# easy_bee_counter.net
KiCad netlist of a schematic drawn in EAGLE
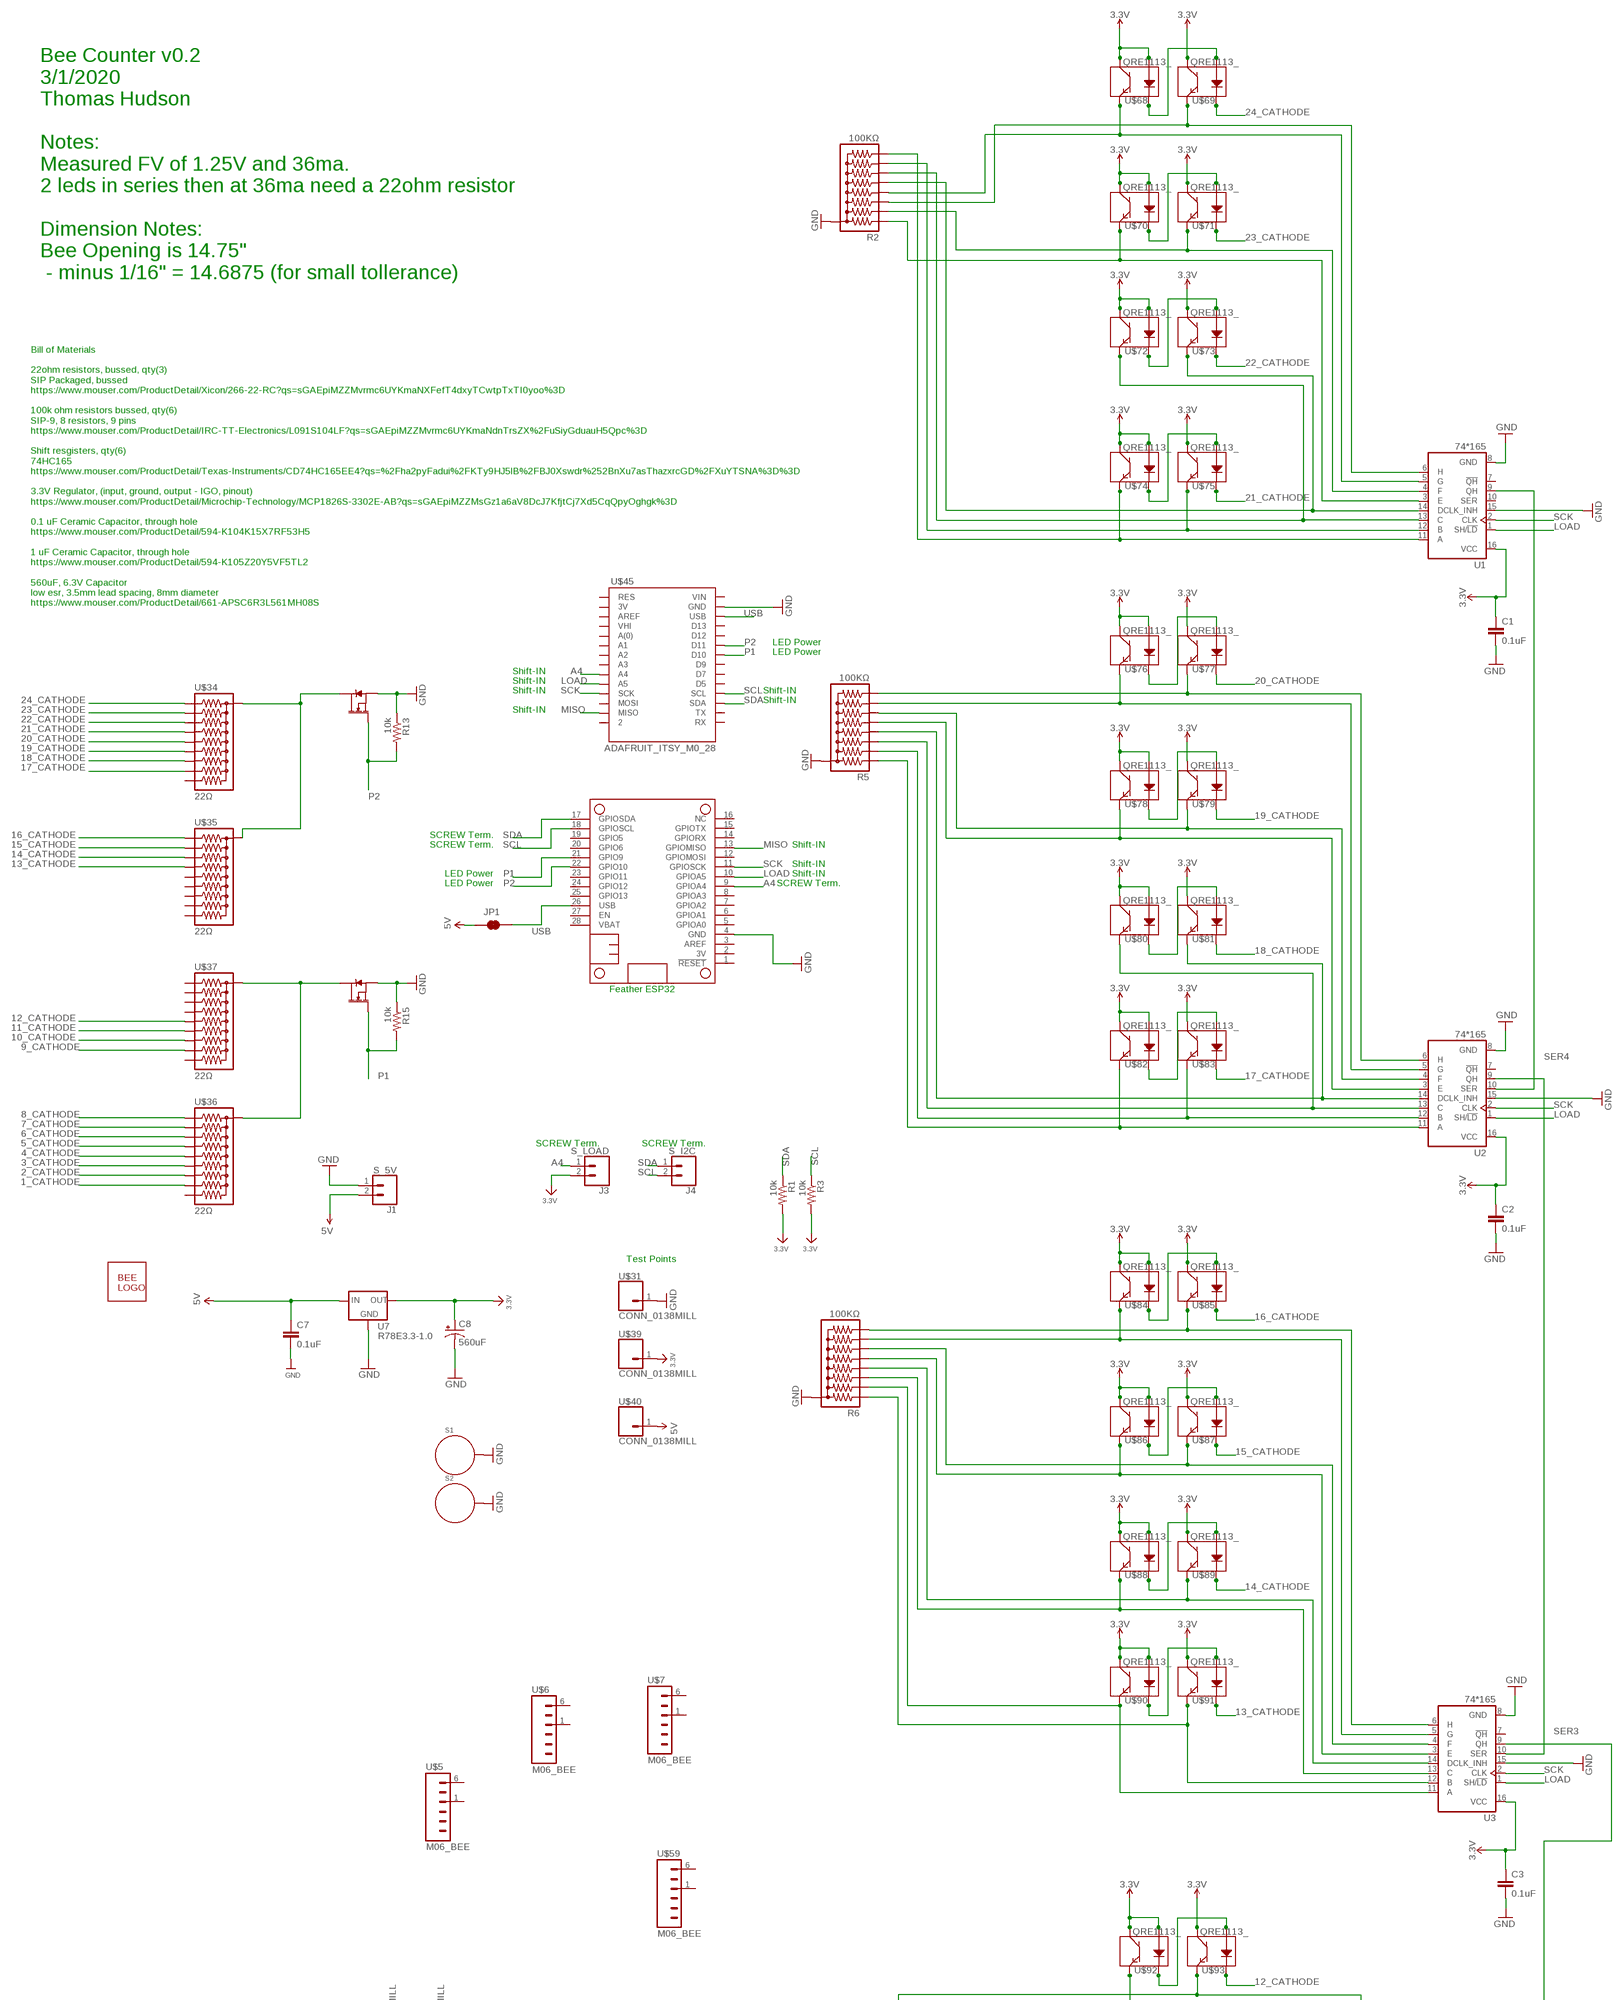
[diagram p0: schematic, sheet 1, part 1 of 2]
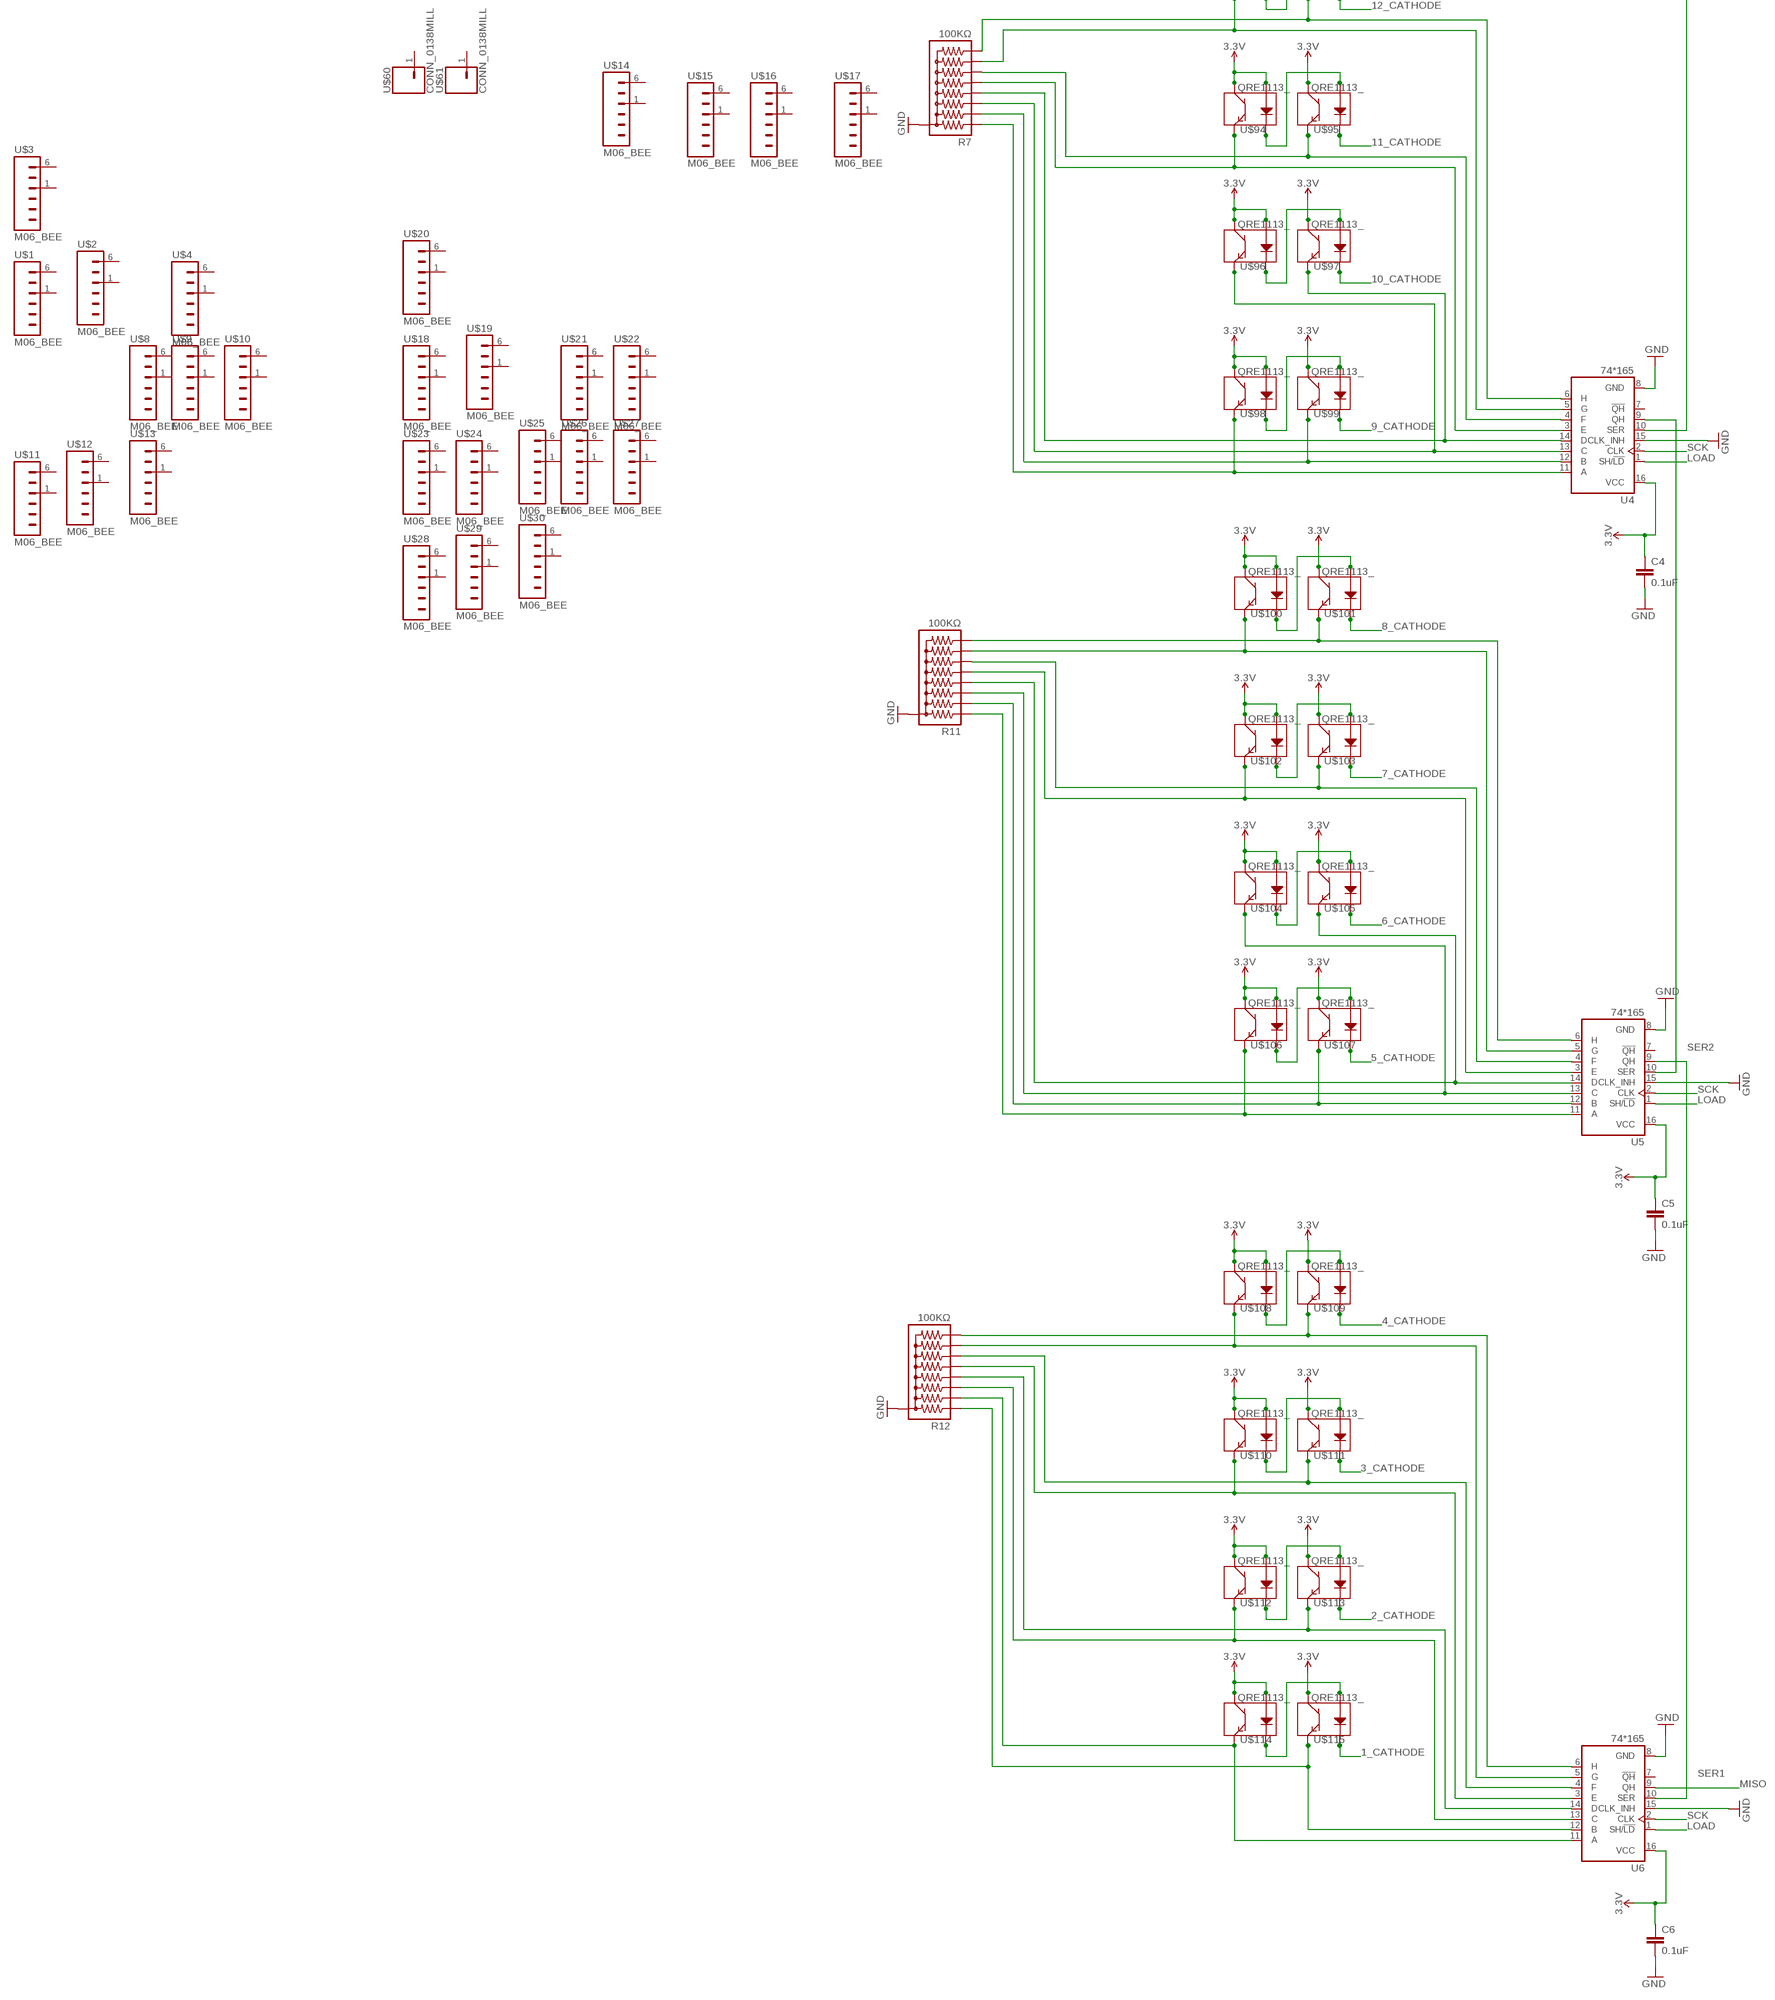
[diagram p1: schematic, sheet 1, part 2 of 2]

(export (version "E")
  (design (tool "Eeschema 10.0.6"))
  (components
    (comp (ref "C1")
      (value "0.1uF")
      (footprint "eagle-import:CAP-PTH-SMALL-KIT")
      (libsource (lib "eagle-import") (part "0.1UF-KIT-EZ-50V-20%"))
    )
    (comp (ref "C2")
      (value "0.1uF")
      (footprint "eagle-import:CAP-PTH-SMALL-KIT")
      (libsource (lib "eagle-import") (part "0.1UF-KIT-EZ-50V-20%"))
    )
    (comp (ref "C3")
      (value "0.1uF")
      (footprint "eagle-import:CAP-PTH-SMALL-KIT")
      (libsource (lib "eagle-import") (part "0.1UF-KIT-EZ-50V-20%"))
    )
    (comp (ref "C4")
      (value "0.1uF")
      (footprint "eagle-import:CAP-PTH-SMALL-KIT")
      (libsource (lib "eagle-import") (part "0.1UF-KIT-EZ-50V-20%"))
    )
    (comp (ref "C5")
      (value "0.1uF")
      (footprint "eagle-import:CAP-PTH-SMALL-KIT")
      (libsource (lib "eagle-import") (part "0.1UF-KIT-EZ-50V-20%"))
    )
    (comp (ref "C6")
      (value "0.1uF")
      (footprint "eagle-import:CAP-PTH-SMALL-KIT")
      (libsource (lib "eagle-import") (part "0.1UF-KIT-EZ-50V-20%"))
    )
    (comp (ref "C7")
      (value "0.1uF")
      (footprint "eagle-import:CAP-PTH-SMALL-KIT")
      (libsource (lib "eagle-import") (part "0.1UF-KIT-EZ-50V-20%"))
    )
    (comp (ref "C8")
      (value "560uF")
      (footprint "eagle-import:E3,5-8")
      (libsource (lib "eagle-import") (part "CPOL-USE3.5-8"))
    )
    (comp (ref "J1")
      (value "S_5V")
      (footprint "eagle-import:SCREWTERMINAL-5MM-2")
      (libsource (lib "eagle-import") (part "CONN_025MM"))
    )
    (comp (ref "J3")
      (value "S_LOAD")
      (footprint "eagle-import:SCREWTERMINAL-5MM-2")
      (libsource (lib "eagle-import") (part "CONN_025MM"))
    )
    (comp (ref "J4")
      (value "S_I2C")
      (footprint "eagle-import:SCREWTERMINAL-5MM-2")
      (libsource (lib "eagle-import") (part "CONN_025MM"))
    )
    (comp (ref "JP1")
      (value "JUMPER-SMT_2_NC_TRACE_SILK")
      (footprint "eagle-import:SMT-JUMPER_2_NC_TRACE_SILK")
      (libsource (lib "eagle-import") (part "JUMPER-SMT_2_NC_TRACE_SILK"))
    )
    (comp (ref "MS2")
      (value "FEATHERWING_NODIM")
      (footprint "eagle-import:FEATHERWING_DIM")
      (libsource (lib "eagle-import") (part "FEATHERWING_NODIM"))
    )
    (comp (ref "Q6")
      (value "60V/32A/35mΩ")
      (footprint "eagle-import:TO220V")
      (libsource (lib "eagle-import") (part "MOSFET-NCH-FQP30N06L"))
    )
    (comp (ref "Q7")
      (value "60V/32A/35mΩ")
      (footprint "eagle-import:TO220V")
      (libsource (lib "eagle-import") (part "MOSFET-NCH-FQP30N06L"))
    )
    (comp (ref "R1")
      (value "10k")
      (footprint "eagle-import:AXIAL-0.3")
      (libsource (lib "eagle-import") (part "RESISTORAXIAL-0.3"))
    )
    (comp (ref "R2")
      (value "100KΩ")
      (footprint "eagle-import:RPACK-SIP-PTH-8")
      (libsource (lib "eagle-import") (part "RPACK-BUSSED-8-SIP-PTH-8"))
    )
    (comp (ref "R3")
      (value "10k")
      (footprint "eagle-import:AXIAL-0.3")
      (libsource (lib "eagle-import") (part "RESISTORAXIAL-0.3"))
    )
    (comp (ref "R5")
      (value "100KΩ")
      (footprint "eagle-import:RPACK-SIP-PTH-8")
      (libsource (lib "eagle-import") (part "RPACK-BUSSED-8-SIP-PTH-8"))
    )
    (comp (ref "R6")
      (value "100KΩ")
      (footprint "eagle-import:RPACK-SIP-PTH-8")
      (libsource (lib "eagle-import") (part "RPACK-BUSSED-8-SIP-PTH-8"))
    )
    (comp (ref "R7")
      (value "100KΩ")
      (footprint "eagle-import:RPACK-SIP-PTH-8")
      (libsource (lib "eagle-import") (part "RPACK-BUSSED-8-SIP-PTH-8"))
    )
    (comp (ref "R11")
      (value "100KΩ")
      (footprint "eagle-import:RPACK-SIP-PTH-8")
      (libsource (lib "eagle-import") (part "RPACK-BUSSED-8-SIP-PTH-8"))
    )
    (comp (ref "R12")
      (value "100KΩ")
      (footprint "eagle-import:RPACK-SIP-PTH-8")
      (libsource (lib "eagle-import") (part "RPACK-BUSSED-8-SIP-PTH-8"))
    )
    (comp (ref "R13")
      (value "10k")
      (footprint "eagle-import:AXIAL-0.3")
      (libsource (lib "eagle-import") (part "RESISTORAXIAL-0.3"))
    )
    (comp (ref "R15")
      (value "10k")
      (footprint "eagle-import:AXIAL-0.3")
      (libsource (lib "eagle-import") (part "RESISTORAXIAL-0.3"))
    )
    (comp (ref "S1")
      (value "STANDOFF_ELECTRICAL5-32")
      (footprint "eagle-import:STANDOFF_ELECTRICAL_5_32")
      (libsource (lib "eagle-import") (part "STANDOFF_ELECTRICAL5-32"))
    )
    (comp (ref "S2")
      (value "STANDOFF_ELECTRICAL5-32")
      (footprint "eagle-import:STANDOFF_ELECTRICAL_5_32")
      (libsource (lib "eagle-import") (part "STANDOFF_ELECTRICAL5-32"))
    )
    (comp (ref "U$1")
      (value "M06_BEE")
      (footprint "eagle-import:1X06_BEE")
      (libsource (lib "eagle-import") (part "M06_BEE"))
    )
    (comp (ref "U$2")
      (value "M06_BEE")
      (footprint "eagle-import:1X06_BEE")
      (libsource (lib "eagle-import") (part "M06_BEE"))
    )
    (comp (ref "U$3")
      (value "M06_BEE")
      (footprint "eagle-import:1X06_BEE")
      (libsource (lib "eagle-import") (part "M06_BEE"))
    )
    (comp (ref "U$4")
      (value "M06_BEE")
      (footprint "eagle-import:1X06_BEE")
      (libsource (lib "eagle-import") (part "M06_BEE"))
    )
    (comp (ref "U$5")
      (value "M06_BEE")
      (footprint "eagle-import:1X06_BEE")
      (libsource (lib "eagle-import") (part "M06_BEE"))
    )
    (comp (ref "U$6")
      (value "M06_BEE")
      (footprint "eagle-import:1X06_BEE")
      (libsource (lib "eagle-import") (part "M06_BEE"))
    )
    (comp (ref "U$7")
      (value "M06_BEE")
      (footprint "eagle-import:1X06_BEE")
      (libsource (lib "eagle-import") (part "M06_BEE"))
    )
    (comp (ref "U$8")
      (value "M06_BEE")
      (footprint "eagle-import:1X06_BEE")
      (libsource (lib "eagle-import") (part "M06_BEE"))
    )
    (comp (ref "U$9")
      (value "M06_BEE")
      (footprint "eagle-import:1X06_BEE")
      (libsource (lib "eagle-import") (part "M06_BEE"))
    )
    (comp (ref "U$10")
      (value "M06_BEE")
      (footprint "eagle-import:1X06_BEE")
      (libsource (lib "eagle-import") (part "M06_BEE"))
    )
    (comp (ref "U$11")
      (value "M06_BEE")
      (footprint "eagle-import:1X06_BEE")
      (libsource (lib "eagle-import") (part "M06_BEE"))
    )
    (comp (ref "U$12")
      (value "M06_BEE")
      (footprint "eagle-import:1X06_BEE")
      (libsource (lib "eagle-import") (part "M06_BEE"))
    )
    (comp (ref "U$13")
      (value "M06_BEE")
      (footprint "eagle-import:1X06_BEE")
      (libsource (lib "eagle-import") (part "M06_BEE"))
    )
    (comp (ref "U$14")
      (value "M06_BEE")
      (footprint "eagle-import:1X06_BEE")
      (libsource (lib "eagle-import") (part "M06_BEE"))
    )
    (comp (ref "U$15")
      (value "M06_BEE")
      (footprint "eagle-import:1X06_BEE")
      (libsource (lib "eagle-import") (part "M06_BEE"))
    )
    (comp (ref "U$16")
      (value "M06_BEE")
      (footprint "eagle-import:1X06_BEE")
      (libsource (lib "eagle-import") (part "M06_BEE"))
    )
    (comp (ref "U$17")
      (value "M06_BEE")
      (footprint "eagle-import:1X06_BEE")
      (libsource (lib "eagle-import") (part "M06_BEE"))
    )
    (comp (ref "U$18")
      (value "M06_BEE")
      (footprint "eagle-import:1X06_BEE")
      (libsource (lib "eagle-import") (part "M06_BEE"))
    )
    (comp (ref "U$19")
      (value "M06_BEE")
      (footprint "eagle-import:1X06_BEE")
      (libsource (lib "eagle-import") (part "M06_BEE"))
    )
    (comp (ref "U$20")
      (value "M06_BEE")
      (footprint "eagle-import:1X06_BEE")
      (libsource (lib "eagle-import") (part "M06_BEE"))
    )
    (comp (ref "U$21")
      (value "M06_BEE")
      (footprint "eagle-import:1X06_BEE")
      (libsource (lib "eagle-import") (part "M06_BEE"))
    )
    (comp (ref "U$22")
      (value "M06_BEE")
      (footprint "eagle-import:1X06_BEE")
      (libsource (lib "eagle-import") (part "M06_BEE"))
    )
    (comp (ref "U$23")
      (value "M06_BEE")
      (footprint "eagle-import:1X06_BEE")
      (libsource (lib "eagle-import") (part "M06_BEE"))
    )
    (comp (ref "U$24")
      (value "M06_BEE")
      (footprint "eagle-import:1X06_BEE")
      (libsource (lib "eagle-import") (part "M06_BEE"))
    )
    (comp (ref "U$25")
      (value "M06_BEE")
      (footprint "eagle-import:1X06_BEE")
      (libsource (lib "eagle-import") (part "M06_BEE"))
    )
    (comp (ref "U$26")
      (value "M06_BEE")
      (footprint "eagle-import:1X06_BEE")
      (libsource (lib "eagle-import") (part "M06_BEE"))
    )
    (comp (ref "U$27")
      (value "M06_BEE")
      (footprint "eagle-import:1X06_BEE")
      (libsource (lib "eagle-import") (part "M06_BEE"))
    )
    (comp (ref "U$28")
      (value "M06_BEE")
      (footprint "eagle-import:1X06_BEE")
      (libsource (lib "eagle-import") (part "M06_BEE"))
    )
    (comp (ref "U$29")
      (value "M06_BEE")
      (footprint "eagle-import:1X06_BEE")
      (libsource (lib "eagle-import") (part "M06_BEE"))
    )
    (comp (ref "U$30")
      (value "M06_BEE")
      (footprint "eagle-import:1X06_BEE")
      (libsource (lib "eagle-import") (part "M06_BEE"))
    )
    (comp (ref "U$31")
      (value "CONN_0138MILL")
      (footprint "eagle-import:1X01-40MILL")
      (libsource (lib "eagle-import") (part "CONN_0138MILL"))
    )
    (comp (ref "U$34")
      (value "22Ω")
      (footprint "eagle-import:RPACK-SIP-PTH-9")
      (libsource (lib "eagle-import") (part "RPACK-BUSSED-9"))
    )
    (comp (ref "U$35")
      (value "22Ω")
      (footprint "eagle-import:RPACK-SIP-PTH-9")
      (libsource (lib "eagle-import") (part "RPACK-BUSSED-9"))
    )
    (comp (ref "U$36")
      (value "22Ω")
      (footprint "eagle-import:RPACK-SIP-PTH-9")
      (libsource (lib "eagle-import") (part "RPACK-BUSSED-9"))
    )
    (comp (ref "U$37")
      (value "22Ω")
      (footprint "eagle-import:RPACK-SIP-PTH-9")
      (libsource (lib "eagle-import") (part "RPACK-BUSSED-9"))
    )
    (comp (ref "U$39")
      (value "CONN_0138MILL")
      (footprint "eagle-import:1X01-40MILL")
      (libsource (lib "eagle-import") (part "CONN_0138MILL"))
    )
    (comp (ref "U$40")
      (value "CONN_0138MILL")
      (footprint "eagle-import:1X01-40MILL")
      (libsource (lib "eagle-import") (part "CONN_0138MILL"))
    )
    (comp (ref "U$44")
      (value "BEE_LOGO")
      (footprint "eagle-import:BEE_LOGO")
      (libsource (lib "eagle-import") (part "BEE_LOGO"))
    )
    (comp (ref "U$45")
      (value "ADAFRUIT_ITSY_M0_28")
      (footprint "eagle-import:ADAFRUIT_ITS_MO_28")
      (libsource (lib "eagle-import") (part "ADAFRUIT_ITSY_M0_28"))
    )
    (comp (ref "U$59")
      (value "M06_BEE")
      (footprint "eagle-import:1X06_BEE")
      (libsource (lib "eagle-import") (part "M06_BEE"))
    )
    (comp (ref "U$60")
      (value "CONN_0138MILL")
      (footprint "eagle-import:1X01-40MILL")
      (libsource (lib "eagle-import") (part "CONN_0138MILL"))
    )
    (comp (ref "U$61")
      (value "CONN_0138MILL")
      (footprint "eagle-import:1X01-40MILL")
      (libsource (lib "eagle-import") (part "CONN_0138MILL"))
    )
    (comp (ref "U$68")
      (value "QRE1113_")
      (footprint "eagle-import:DIP400W50P180L360H200Q4")
      (libsource (lib "eagle-import") (part "QRE1113_"))
    )
    (comp (ref "U$69")
      (value "QRE1113_")
      (footprint "eagle-import:DIP400W50P180L360H200Q4")
      (libsource (lib "eagle-import") (part "QRE1113_"))
    )
    (comp (ref "U$70")
      (value "QRE1113_")
      (footprint "eagle-import:DIP400W50P180L360H200Q4")
      (libsource (lib "eagle-import") (part "QRE1113_"))
    )
    (comp (ref "U$71")
      (value "QRE1113_")
      (footprint "eagle-import:DIP400W50P180L360H200Q4")
      (libsource (lib "eagle-import") (part "QRE1113_"))
    )
    (comp (ref "U$72")
      (value "QRE1113_")
      (footprint "eagle-import:DIP400W50P180L360H200Q4")
      (libsource (lib "eagle-import") (part "QRE1113_"))
    )
    (comp (ref "U$73")
      (value "QRE1113_")
      (footprint "eagle-import:DIP400W50P180L360H200Q4")
      (libsource (lib "eagle-import") (part "QRE1113_"))
    )
    (comp (ref "U$74")
      (value "QRE1113_")
      (footprint "eagle-import:DIP400W50P180L360H200Q4")
      (libsource (lib "eagle-import") (part "QRE1113_"))
    )
    (comp (ref "U$75")
      (value "QRE1113_")
      (footprint "eagle-import:DIP400W50P180L360H200Q4")
      (libsource (lib "eagle-import") (part "QRE1113_"))
    )
    (comp (ref "U$76")
      (value "QRE1113_")
      (footprint "eagle-import:DIP400W50P180L360H200Q4")
      (libsource (lib "eagle-import") (part "QRE1113_"))
    )
    (comp (ref "U$77")
      (value "QRE1113_")
      (footprint "eagle-import:DIP400W50P180L360H200Q4")
      (libsource (lib "eagle-import") (part "QRE1113_"))
    )
    (comp (ref "U$78")
      (value "QRE1113_")
      (footprint "eagle-import:DIP400W50P180L360H200Q4")
      (libsource (lib "eagle-import") (part "QRE1113_"))
    )
    (comp (ref "U$79")
      (value "QRE1113_")
      (footprint "eagle-import:DIP400W50P180L360H200Q4")
      (libsource (lib "eagle-import") (part "QRE1113_"))
    )
    (comp (ref "U$80")
      (value "QRE1113_")
      (footprint "eagle-import:DIP400W50P180L360H200Q4")
      (libsource (lib "eagle-import") (part "QRE1113_"))
    )
    (comp (ref "U$81")
      (value "QRE1113_")
      (footprint "eagle-import:DIP400W50P180L360H200Q4")
      (libsource (lib "eagle-import") (part "QRE1113_"))
    )
    (comp (ref "U$82")
      (value "QRE1113_")
      (footprint "eagle-import:DIP400W50P180L360H200Q4")
      (libsource (lib "eagle-import") (part "QRE1113_"))
    )
    (comp (ref "U$83")
      (value "QRE1113_")
      (footprint "eagle-import:DIP400W50P180L360H200Q4")
      (libsource (lib "eagle-import") (part "QRE1113_"))
    )
    (comp (ref "U$84")
      (value "QRE1113_")
      (footprint "eagle-import:DIP400W50P180L360H200Q4")
      (libsource (lib "eagle-import") (part "QRE1113_"))
    )
    (comp (ref "U$85")
      (value "QRE1113_")
      (footprint "eagle-import:DIP400W50P180L360H200Q4")
      (libsource (lib "eagle-import") (part "QRE1113_"))
    )
    (comp (ref "U$86")
      (value "QRE1113_")
      (footprint "eagle-import:DIP400W50P180L360H200Q4")
      (libsource (lib "eagle-import") (part "QRE1113_"))
    )
    (comp (ref "U$87")
      (value "QRE1113_")
      (footprint "eagle-import:DIP400W50P180L360H200Q4")
      (libsource (lib "eagle-import") (part "QRE1113_"))
    )
    (comp (ref "U$88")
      (value "QRE1113_")
      (footprint "eagle-import:DIP400W50P180L360H200Q4")
      (libsource (lib "eagle-import") (part "QRE1113_"))
    )
    (comp (ref "U$89")
      (value "QRE1113_")
      (footprint "eagle-import:DIP400W50P180L360H200Q4")
      (libsource (lib "eagle-import") (part "QRE1113_"))
    )
    (comp (ref "U$90")
      (value "QRE1113_")
      (footprint "eagle-import:DIP400W50P180L360H200Q4")
      (libsource (lib "eagle-import") (part "QRE1113_"))
    )
    (comp (ref "U$91")
      (value "QRE1113_")
      (footprint "eagle-import:DIP400W50P180L360H200Q4")
      (libsource (lib "eagle-import") (part "QRE1113_"))
    )
    (comp (ref "U$92")
      (value "QRE1113_")
      (footprint "eagle-import:DIP400W50P180L360H200Q4")
      (libsource (lib "eagle-import") (part "QRE1113_"))
    )
    (comp (ref "U$93")
      (value "QRE1113_")
      (footprint "eagle-import:DIP400W50P180L360H200Q4")
      (libsource (lib "eagle-import") (part "QRE1113_"))
    )
    (comp (ref "U$94")
      (value "QRE1113_")
      (footprint "eagle-import:DIP400W50P180L360H200Q4")
      (libsource (lib "eagle-import") (part "QRE1113_"))
    )
    (comp (ref "U$95")
      (value "QRE1113_")
      (footprint "eagle-import:DIP400W50P180L360H200Q4")
      (libsource (lib "eagle-import") (part "QRE1113_"))
    )
    (comp (ref "U$96")
      (value "QRE1113_")
      (footprint "eagle-import:DIP400W50P180L360H200Q4")
      (libsource (lib "eagle-import") (part "QRE1113_"))
    )
    (comp (ref "U$97")
      (value "QRE1113_")
      (footprint "eagle-import:DIP400W50P180L360H200Q4")
      (libsource (lib "eagle-import") (part "QRE1113_"))
    )
    (comp (ref "U$98")
      (value "QRE1113_")
      (footprint "eagle-import:DIP400W50P180L360H200Q4")
      (libsource (lib "eagle-import") (part "QRE1113_"))
    )
    (comp (ref "U$99")
      (value "QRE1113_")
      (footprint "eagle-import:DIP400W50P180L360H200Q4")
      (libsource (lib "eagle-import") (part "QRE1113_"))
    )
    (comp (ref "U$100")
      (value "QRE1113_")
      (footprint "eagle-import:DIP400W50P180L360H200Q4")
      (libsource (lib "eagle-import") (part "QRE1113_"))
    )
    (comp (ref "U$101")
      (value "QRE1113_")
      (footprint "eagle-import:DIP400W50P180L360H200Q4")
      (libsource (lib "eagle-import") (part "QRE1113_"))
    )
    (comp (ref "U$102")
      (value "QRE1113_")
      (footprint "eagle-import:DIP400W50P180L360H200Q4")
      (libsource (lib "eagle-import") (part "QRE1113_"))
    )
    (comp (ref "U$103")
      (value "QRE1113_")
      (footprint "eagle-import:DIP400W50P180L360H200Q4")
      (libsource (lib "eagle-import") (part "QRE1113_"))
    )
    (comp (ref "U$104")
      (value "QRE1113_")
      (footprint "eagle-import:DIP400W50P180L360H200Q4")
      (libsource (lib "eagle-import") (part "QRE1113_"))
    )
    (comp (ref "U$105")
      (value "QRE1113_")
      (footprint "eagle-import:DIP400W50P180L360H200Q4")
      (libsource (lib "eagle-import") (part "QRE1113_"))
    )
    (comp (ref "U$106")
      (value "QRE1113_")
      (footprint "eagle-import:DIP400W50P180L360H200Q4")
      (libsource (lib "eagle-import") (part "QRE1113_"))
    )
    (comp (ref "U$107")
      (value "QRE1113_")
      (footprint "eagle-import:DIP400W50P180L360H200Q4")
      (libsource (lib "eagle-import") (part "QRE1113_"))
    )
    (comp (ref "U$108")
      (value "QRE1113_")
      (footprint "eagle-import:DIP400W50P180L360H200Q4")
      (libsource (lib "eagle-import") (part "QRE1113_"))
    )
    (comp (ref "U$109")
      (value "QRE1113_")
      (footprint "eagle-import:DIP400W50P180L360H200Q4")
      (libsource (lib "eagle-import") (part "QRE1113_"))
    )
    (comp (ref "U$110")
      (value "QRE1113_")
      (footprint "eagle-import:DIP400W50P180L360H200Q4")
      (libsource (lib "eagle-import") (part "QRE1113_"))
    )
    (comp (ref "U$111")
      (value "QRE1113_")
      (footprint "eagle-import:DIP400W50P180L360H200Q4")
      (libsource (lib "eagle-import") (part "QRE1113_"))
    )
    (comp (ref "U$112")
      (value "QRE1113_")
      (footprint "eagle-import:DIP400W50P180L360H200Q4")
      (libsource (lib "eagle-import") (part "QRE1113_"))
    )
    (comp (ref "U$113")
      (value "QRE1113_")
      (footprint "eagle-import:DIP400W50P180L360H200Q4")
      (libsource (lib "eagle-import") (part "QRE1113_"))
    )
    (comp (ref "U$114")
      (value "QRE1113_")
      (footprint "eagle-import:DIP400W50P180L360H200Q4")
      (libsource (lib "eagle-import") (part "QRE1113_"))
    )
    (comp (ref "U$115")
      (value "QRE1113_")
      (footprint "eagle-import:DIP400W50P180L360H200Q4")
      (libsource (lib "eagle-import") (part "QRE1113_"))
    )
    (comp (ref "U1")
      (value "74*165")
      (footprint "eagle-import:DIP16")
      (libsource (lib "eagle-import") (part "74165"))
    )
    (comp (ref "U2")
      (value "74*165")
      (footprint "eagle-import:DIP16")
      (libsource (lib "eagle-import") (part "74165"))
    )
    (comp (ref "U3")
      (value "74*165")
      (footprint "eagle-import:DIP16")
      (libsource (lib "eagle-import") (part "74165"))
    )
    (comp (ref "U4")
      (value "74*165")
      (footprint "eagle-import:DIP16")
      (libsource (lib "eagle-import") (part "74165"))
    )
    (comp (ref "U5")
      (value "74*165")
      (footprint "eagle-import:DIP16")
      (libsource (lib "eagle-import") (part "74165"))
    )
    (comp (ref "U6")
      (value "74*165")
      (footprint "eagle-import:DIP16")
      (libsource (lib "eagle-import") (part "74165"))
    )
    (comp (ref "U7")
      (value "R78E3.3-1.0")
      (footprint "eagle-import:DC-DC_CONVERTER_78XX")
      (libsource (lib "eagle-import") (part "R-78E5.0-1.0"))
    )
  )
  (nets
    (net (code "1") (name "/1_CATHODE") (class "Default")
      (node (ref "U$115") (pin "2") (pinfunction "K_2") (pintype "bidirectional"))
      (node (ref "U$36") (pin "P$9") (pinfunction "9_P$9") (pintype "passive"))
    )
    (net (code "2") (name "/2_CATHODE") (class "Default")
      (node (ref "U$113") (pin "2") (pinfunction "K_2") (pintype "bidirectional"))
      (node (ref "U$36") (pin "P$8") (pinfunction "8_P$8") (pintype "passive"))
    )
    (net (code "3") (name "/3V") (class "Default")
      (node (ref "MS2") (pin "2") (pinfunction "3V_2") (pintype "power_in"))
    )
    (net (code "4") (name "/3_CATHODE") (class "Default")
      (node (ref "U$111") (pin "2") (pinfunction "K_2") (pintype "bidirectional"))
      (node (ref "U$36") (pin "P$7") (pinfunction "7_P$7") (pintype "passive"))
    )
    (net (code "5") (name "/4_CATHODE") (class "Default")
      (node (ref "U$109") (pin "2") (pinfunction "K_2") (pintype "bidirectional"))
      (node (ref "U$36") (pin "P$6") (pinfunction "6_P$6") (pintype "passive"))
    )
    (net (code "6") (name "/5_CATHODE") (class "Default")
      (node (ref "U$107") (pin "2") (pinfunction "K_2") (pintype "bidirectional"))
      (node (ref "U$36") (pin "P$5") (pinfunction "5_P$5") (pintype "passive"))
    )
    (net (code "7") (name "/6_CATHODE") (class "Default")
      (node (ref "U$105") (pin "2") (pinfunction "K_2") (pintype "bidirectional"))
      (node (ref "U$36") (pin "P$4") (pinfunction "4_P$4") (pintype "passive"))
    )
    (net (code "8") (name "/7_CATHODE") (class "Default")
      (node (ref "U$103") (pin "2") (pinfunction "K_2") (pintype "bidirectional"))
      (node (ref "U$36") (pin "P$3") (pinfunction "3_P$3") (pintype "passive"))
    )
    (net (code "9") (name "/8_CATHODE") (class "Default")
      (node (ref "U$101") (pin "2") (pinfunction "K_2") (pintype "bidirectional"))
      (node (ref "U$36") (pin "P$2") (pinfunction "2_P$2") (pintype "passive"))
    )
    (net (code "10") (name "/9_CATHODE") (class "Default")
      (node (ref "U$37") (pin "P$9") (pinfunction "9_P$9") (pintype "passive"))
      (node (ref "U$99") (pin "2") (pinfunction "K_2") (pintype "bidirectional"))
    )
    (net (code "11") (name "/10_CATHODE") (class "Default")
      (node (ref "U$37") (pin "P$8") (pinfunction "8_P$8") (pintype "passive"))
      (node (ref "U$97") (pin "2") (pinfunction "K_2") (pintype "bidirectional"))
    )
    (net (code "12") (name "/11_CATHODE") (class "Default")
      (node (ref "U$37") (pin "P$7") (pinfunction "7_P$7") (pintype "passive"))
      (node (ref "U$95") (pin "2") (pinfunction "K_2") (pintype "bidirectional"))
    )
    (net (code "13") (name "/12_CATHODE") (class "Default")
      (node (ref "U$37") (pin "P$6") (pinfunction "6_P$6") (pintype "passive"))
      (node (ref "U$93") (pin "2") (pinfunction "K_2") (pintype "bidirectional"))
    )
    (net (code "14") (name "/13_CATHODE") (class "Default")
      (node (ref "U$35") (pin "P$5") (pinfunction "5_P$5") (pintype "passive"))
      (node (ref "U$91") (pin "2") (pinfunction "K_2") (pintype "bidirectional"))
    )
    (net (code "15") (name "/14_CATHODE") (class "Default")
      (node (ref "U$35") (pin "P$4") (pinfunction "4_P$4") (pintype "passive"))
      (node (ref "U$89") (pin "2") (pinfunction "K_2") (pintype "bidirectional"))
    )
    (net (code "16") (name "/15_CATHODE") (class "Default")
      (node (ref "U$35") (pin "P$3") (pinfunction "3_P$3") (pintype "passive"))
      (node (ref "U$87") (pin "2") (pinfunction "K_2") (pintype "bidirectional"))
    )
    (net (code "17") (name "/16_CATHODE") (class "Default")
      (node (ref "U$35") (pin "P$2") (pinfunction "2_P$2") (pintype "passive"))
      (node (ref "U$85") (pin "2") (pinfunction "K_2") (pintype "bidirectional"))
    )
    (net (code "18") (name "/17_CATHODE") (class "Default")
      (node (ref "U$34") (pin "P$9") (pinfunction "9_P$9") (pintype "passive"))
      (node (ref "U$83") (pin "2") (pinfunction "K_2") (pintype "bidirectional"))
    )
    (net (code "19") (name "/18_CATHODE") (class "Default")
      (node (ref "U$34") (pin "P$8") (pinfunction "8_P$8") (pintype "passive"))
      (node (ref "U$81") (pin "2") (pinfunction "K_2") (pintype "bidirectional"))
    )
    (net (code "20") (name "/19_CATHODE") (class "Default")
      (node (ref "U$34") (pin "P$7") (pinfunction "7_P$7") (pintype "passive"))
      (node (ref "U$79") (pin "2") (pinfunction "K_2") (pintype "bidirectional"))
    )
    (net (code "21") (name "/20_CATHODE") (class "Default")
      (node (ref "U$34") (pin "P$6") (pinfunction "6_P$6") (pintype "passive"))
      (node (ref "U$77") (pin "2") (pinfunction "K_2") (pintype "bidirectional"))
    )
    (net (code "22") (name "/21_CATHODE") (class "Default")
      (node (ref "U$34") (pin "P$5") (pinfunction "5_P$5") (pintype "passive"))
      (node (ref "U$75") (pin "2") (pinfunction "K_2") (pintype "bidirectional"))
    )
    (net (code "23") (name "/22_CATHODE") (class "Default")
      (node (ref "U$34") (pin "P$4") (pinfunction "4_P$4") (pintype "passive"))
      (node (ref "U$73") (pin "2") (pinfunction "K_2") (pintype "bidirectional"))
    )
    (net (code "24") (name "/23_CATHODE") (class "Default")
      (node (ref "U$34") (pin "P$3") (pinfunction "3_P$3") (pintype "passive"))
      (node (ref "U$71") (pin "2") (pinfunction "K_2") (pintype "bidirectional"))
    )
    (net (code "25") (name "/24_CATHODE") (class "Default")
      (node (ref "U$34") (pin "P$2") (pinfunction "2_P$2") (pintype "passive"))
      (node (ref "U$69") (pin "2") (pinfunction "K_2") (pintype "bidirectional"))
    )
    (net (code "26") (name "/A4") (class "Default")
      (node (ref "J3") (pin "1") (pinfunction "1_1") (pintype "passive"))
      (node (ref "MS2") (pin "9") (pinfunction "GPIOA4_9") (pintype "bidirectional"))
      (node (ref "U$45") (pin "A4") (pinfunction "A4_A4") (pintype "bidirectional"))
    )
    (net (code "27") (name "/LOAD") (class "Default")
      (node (ref "MS2") (pin "10") (pinfunction "GPIOA5_10") (pintype "bidirectional"))
      (node (ref "U$45") (pin "A5") (pinfunction "A5_A5") (pintype "bidirectional"))
      (node (ref "U1") (pin "1") (pinfunction "SH/~{LD}_1") (pintype "input"))
      (node (ref "U2") (pin "1") (pinfunction "SH/~{LD}_1") (pintype "input"))
      (node (ref "U3") (pin "1") (pinfunction "SH/~{LD}_1") (pintype "input"))
      (node (ref "U4") (pin "1") (pinfunction "SH/~{LD}_1") (pintype "input"))
      (node (ref "U5") (pin "1") (pinfunction "SH/~{LD}_1") (pintype "input"))
      (node (ref "U6") (pin "1") (pinfunction "SH/~{LD}_1") (pintype "input"))
    )
    (net (code "28") (name "/MISO") (class "Default")
      (node (ref "MS2") (pin "13") (pinfunction "GPIOMISO_13") (pintype "bidirectional"))
      (node (ref "U$45") (pin "MISO") (pinfunction "MISO_MISO") (pintype "bidirectional"))
      (node (ref "U6") (pin "9") (pinfunction "QH_9") (pintype "tri_state"))
    )
    (net (code "29") (name "/P1") (class "Default")
      (node (ref "MS2") (pin "21") (pinfunction "GPIO9_21") (pintype "bidirectional"))
      (node (ref "Q7") (pin "1") (pinfunction "G_1") (pintype "bidirectional"))
      (node (ref "R15") (pin "P$2") (pinfunction "2_P$2") (pintype "passive"))
      (node (ref "U$45") (pin "D10") (pinfunction "D10_D10") (pintype "bidirectional"))
    )
    (net (code "30") (name "/P2") (class "Default")
      (node (ref "MS2") (pin "22") (pinfunction "GPIO10_22") (pintype "bidirectional"))
      (node (ref "Q6") (pin "1") (pinfunction "G_1") (pintype "bidirectional"))
      (node (ref "R13") (pin "P$2") (pinfunction "2_P$2") (pintype "passive"))
      (node (ref "U$45") (pin "D11") (pinfunction "D11_D11") (pintype "bidirectional"))
    )
    (net (code "31") (name "/SCK") (class "Default")
      (node (ref "MS2") (pin "11") (pinfunction "GPIOSCK_11") (pintype "bidirectional"))
      (node (ref "U$45") (pin "SCK") (pinfunction "SCK_SCK") (pintype "bidirectional"))
      (node (ref "U1") (pin "2") (pinfunction "CLK_2") (pintype "input"))
      (node (ref "U2") (pin "2") (pinfunction "CLK_2") (pintype "input"))
      (node (ref "U3") (pin "2") (pinfunction "CLK_2") (pintype "input"))
      (node (ref "U4") (pin "2") (pinfunction "CLK_2") (pintype "input"))
      (node (ref "U5") (pin "2") (pinfunction "CLK_2") (pintype "input"))
      (node (ref "U6") (pin "2") (pinfunction "CLK_2") (pintype "input"))
    )
    (net (code "32") (name "/SCL") (class "Default")
      (node (ref "J4") (pin "2") (pinfunction "2_2") (pintype "passive"))
      (node (ref "MS2") (pin "18") (pinfunction "GPIOSCL_18") (pintype "bidirectional"))
      (node (ref "R3") (pin "P$1") (pinfunction "1_P$1") (pintype "passive"))
      (node (ref "U$45") (pin "SCL") (pinfunction "SCL_SCL") (pintype "bidirectional"))
    )
    (net (code "33") (name "/SDA") (class "Default")
      (node (ref "J4") (pin "1") (pinfunction "1_1") (pintype "passive"))
      (node (ref "MS2") (pin "17") (pinfunction "GPIOSDA_17") (pintype "bidirectional"))
      (node (ref "R1") (pin "P$1") (pinfunction "1_P$1") (pintype "passive"))
      (node (ref "U$45") (pin "SDA") (pinfunction "SDA_SDA") (pintype "bidirectional"))
    )
    (net (code "34") (name "/SER1") (class "Default")
      (node (ref "U5") (pin "9") (pinfunction "QH_9") (pintype "tri_state"))
      (node (ref "U6") (pin "10") (pinfunction "SER_10") (pintype "input"))
    )
    (net (code "35") (name "/SER2") (class "Default")
      (node (ref "U4") (pin "9") (pinfunction "QH_9") (pintype "tri_state"))
      (node (ref "U5") (pin "10") (pinfunction "SER_10") (pintype "input"))
    )
    (net (code "36") (name "/SER3") (class "Default")
      (node (ref "U2") (pin "9") (pinfunction "QH_9") (pintype "tri_state"))
      (node (ref "U3") (pin "10") (pinfunction "SER_10") (pintype "input"))
    )
    (net (code "37") (name "/SER4") (class "Default")
      (node (ref "U1") (pin "9") (pinfunction "QH_9") (pintype "tri_state"))
      (node (ref "U2") (pin "10") (pinfunction "SER_10") (pintype "input"))
    )
    (net (code "38") (name "/USB") (class "Default")
      (node (ref "JP1") (pin "2") (pinfunction "2_2") (pintype "passive"))
      (node (ref "MS2") (pin "26") (pinfunction "USB_26") (pintype "power_in"))
      (node (ref "U$45") (pin "USB") (pinfunction "USB_USB") (pintype "bidirectional"))
    )
    (net (code "39") (name "/VBAT") (class "Default")
      (node (ref "MS2") (pin "28") (pinfunction "VBAT_28") (pintype "power_in"))
    )
    (net (code "40") (name "3.3V") (class "Default")
      (node (ref "C1") (pin "1") (pinfunction "1_1") (pintype "passive"))
      (node (ref "C2") (pin "1") (pinfunction "1_1") (pintype "passive"))
      (node (ref "C3") (pin "1") (pinfunction "1_1") (pintype "passive"))
      (node (ref "C4") (pin "1") (pinfunction "1_1") (pintype "passive"))
      (node (ref "C5") (pin "1") (pinfunction "1_1") (pintype "passive"))
      (node (ref "C6") (pin "1") (pinfunction "1_1") (pintype "passive"))
      (node (ref "C8") (pin "+") (pinfunction "+_+") (pintype "passive"))
      (node (ref "J3") (pin "2") (pinfunction "2_2") (pintype "passive"))
      (node (ref "R1") (pin "P$2") (pinfunction "2_P$2") (pintype "passive"))
      (node (ref "R3") (pin "P$2") (pinfunction "2_P$2") (pintype "passive"))
      (node (ref "U$100") (pin "1") (pinfunction "A_1") (pintype "bidirectional"))
      (node (ref "U$100") (pin "3") (pinfunction "C_3") (pintype "bidirectional"))
      (node (ref "U$101") (pin "3") (pinfunction "C_3") (pintype "bidirectional"))
      (node (ref "U$102") (pin "1") (pinfunction "A_1") (pintype "bidirectional"))
      (node (ref "U$102") (pin "3") (pinfunction "C_3") (pintype "bidirectional"))
      (node (ref "U$103") (pin "3") (pinfunction "C_3") (pintype "bidirectional"))
      (node (ref "U$104") (pin "1") (pinfunction "A_1") (pintype "bidirectional"))
      (node (ref "U$104") (pin "3") (pinfunction "C_3") (pintype "bidirectional"))
      (node (ref "U$105") (pin "3") (pinfunction "C_3") (pintype "bidirectional"))
      (node (ref "U$106") (pin "1") (pinfunction "A_1") (pintype "bidirectional"))
      (node (ref "U$106") (pin "3") (pinfunction "C_3") (pintype "bidirectional"))
      (node (ref "U$107") (pin "3") (pinfunction "C_3") (pintype "bidirectional"))
      (node (ref "U$108") (pin "1") (pinfunction "A_1") (pintype "bidirectional"))
      (node (ref "U$108") (pin "3") (pinfunction "C_3") (pintype "bidirectional"))
      (node (ref "U$109") (pin "3") (pinfunction "C_3") (pintype "bidirectional"))
      (node (ref "U$110") (pin "1") (pinfunction "A_1") (pintype "bidirectional"))
      (node (ref "U$110") (pin "3") (pinfunction "C_3") (pintype "bidirectional"))
      (node (ref "U$111") (pin "3") (pinfunction "C_3") (pintype "bidirectional"))
      (node (ref "U$112") (pin "1") (pinfunction "A_1") (pintype "bidirectional"))
      (node (ref "U$112") (pin "3") (pinfunction "C_3") (pintype "bidirectional"))
      (node (ref "U$113") (pin "3") (pinfunction "C_3") (pintype "bidirectional"))
      (node (ref "U$114") (pin "1") (pinfunction "A_1") (pintype "bidirectional"))
      (node (ref "U$114") (pin "3") (pinfunction "C_3") (pintype "bidirectional"))
      (node (ref "U$115") (pin "3") (pinfunction "C_3") (pintype "bidirectional"))
      (node (ref "U$39") (pin "1") (pinfunction "1_1") (pintype "passive"))
      (node (ref "U$68") (pin "1") (pinfunction "A_1") (pintype "bidirectional"))
      (node (ref "U$68") (pin "3") (pinfunction "C_3") (pintype "bidirectional"))
      (node (ref "U$69") (pin "3") (pinfunction "C_3") (pintype "bidirectional"))
      (node (ref "U$70") (pin "1") (pinfunction "A_1") (pintype "bidirectional"))
      (node (ref "U$70") (pin "3") (pinfunction "C_3") (pintype "bidirectional"))
      (node (ref "U$71") (pin "3") (pinfunction "C_3") (pintype "bidirectional"))
      (node (ref "U$72") (pin "1") (pinfunction "A_1") (pintype "bidirectional"))
      (node (ref "U$72") (pin "3") (pinfunction "C_3") (pintype "bidirectional"))
      (node (ref "U$73") (pin "3") (pinfunction "C_3") (pintype "bidirectional"))
      (node (ref "U$74") (pin "1") (pinfunction "A_1") (pintype "bidirectional"))
      (node (ref "U$74") (pin "3") (pinfunction "C_3") (pintype "bidirectional"))
      (node (ref "U$75") (pin "3") (pinfunction "C_3") (pintype "bidirectional"))
      (node (ref "U$76") (pin "1") (pinfunction "A_1") (pintype "bidirectional"))
      (node (ref "U$76") (pin "3") (pinfunction "C_3") (pintype "bidirectional"))
      (node (ref "U$77") (pin "3") (pinfunction "C_3") (pintype "bidirectional"))
      (node (ref "U$78") (pin "1") (pinfunction "A_1") (pintype "bidirectional"))
      (node (ref "U$78") (pin "3") (pinfunction "C_3") (pintype "bidirectional"))
      (node (ref "U$79") (pin "3") (pinfunction "C_3") (pintype "bidirectional"))
      (node (ref "U$80") (pin "1") (pinfunction "A_1") (pintype "bidirectional"))
      (node (ref "U$80") (pin "3") (pinfunction "C_3") (pintype "bidirectional"))
      (node (ref "U$81") (pin "3") (pinfunction "C_3") (pintype "bidirectional"))
      (node (ref "U$82") (pin "1") (pinfunction "A_1") (pintype "bidirectional"))
      (node (ref "U$82") (pin "3") (pinfunction "C_3") (pintype "bidirectional"))
      (node (ref "U$83") (pin "3") (pinfunction "C_3") (pintype "bidirectional"))
      (node (ref "U$84") (pin "1") (pinfunction "A_1") (pintype "bidirectional"))
      (node (ref "U$84") (pin "3") (pinfunction "C_3") (pintype "bidirectional"))
      (node (ref "U$85") (pin "3") (pinfunction "C_3") (pintype "bidirectional"))
      (node (ref "U$86") (pin "1") (pinfunction "A_1") (pintype "bidirectional"))
      (node (ref "U$86") (pin "3") (pinfunction "C_3") (pintype "bidirectional"))
      (node (ref "U$87") (pin "3") (pinfunction "C_3") (pintype "bidirectional"))
      (node (ref "U$88") (pin "1") (pinfunction "A_1") (pintype "bidirectional"))
      (node (ref "U$88") (pin "3") (pinfunction "C_3") (pintype "bidirectional"))
      (node (ref "U$89") (pin "3") (pinfunction "C_3") (pintype "bidirectional"))
      (node (ref "U$90") (pin "1") (pinfunction "A_1") (pintype "bidirectional"))
      (node (ref "U$90") (pin "3") (pinfunction "C_3") (pintype "bidirectional"))
      (node (ref "U$91") (pin "3") (pinfunction "C_3") (pintype "bidirectional"))
      (node (ref "U$92") (pin "1") (pinfunction "A_1") (pintype "bidirectional"))
      (node (ref "U$92") (pin "3") (pinfunction "C_3") (pintype "bidirectional"))
      (node (ref "U$93") (pin "3") (pinfunction "C_3") (pintype "bidirectional"))
      (node (ref "U$94") (pin "1") (pinfunction "A_1") (pintype "bidirectional"))
      (node (ref "U$94") (pin "3") (pinfunction "C_3") (pintype "bidirectional"))
      (node (ref "U$95") (pin "3") (pinfunction "C_3") (pintype "bidirectional"))
      (node (ref "U$96") (pin "1") (pinfunction "A_1") (pintype "bidirectional"))
      (node (ref "U$96") (pin "3") (pinfunction "C_3") (pintype "bidirectional"))
      (node (ref "U$97") (pin "3") (pinfunction "C_3") (pintype "bidirectional"))
      (node (ref "U$98") (pin "1") (pinfunction "A_1") (pintype "bidirectional"))
      (node (ref "U$98") (pin "3") (pinfunction "C_3") (pintype "bidirectional"))
      (node (ref "U$99") (pin "3") (pinfunction "C_3") (pintype "bidirectional"))
      (node (ref "U1") (pin "16") (pinfunction "VCC_16") (pintype "power_in"))
      (node (ref "U2") (pin "16") (pinfunction "VCC_16") (pintype "power_in"))
      (node (ref "U3") (pin "16") (pinfunction "VCC_16") (pintype "power_in"))
      (node (ref "U4") (pin "16") (pinfunction "VCC_16") (pintype "power_in"))
      (node (ref "U5") (pin "16") (pinfunction "VCC_16") (pintype "power_in"))
      (node (ref "U6") (pin "16") (pinfunction "VCC_16") (pintype "power_in"))
      (node (ref "U7") (pin "VOUT") (pinfunction "OUT_VOUT") (pintype "passive"))
    )
    (net (code "41") (name "5V") (class "Default")
      (node (ref "C7") (pin "1") (pinfunction "1_1") (pintype "passive"))
      (node (ref "J1") (pin "2") (pinfunction "2_2") (pintype "passive"))
      (node (ref "JP1") (pin "1") (pinfunction "1_1") (pintype "passive"))
      (node (ref "U$40") (pin "1") (pinfunction "1_1") (pintype "passive"))
      (node (ref "U7") (pin "VIN") (pinfunction "IN_VIN") (pintype "input"))
    )
    (net (code "42") (name "GND") (class "Default")
      (node (ref "C1") (pin "2") (pinfunction "2_2") (pintype "passive"))
      (node (ref "C2") (pin "2") (pinfunction "2_2") (pintype "passive"))
      (node (ref "C3") (pin "2") (pinfunction "2_2") (pintype "passive"))
      (node (ref "C4") (pin "2") (pinfunction "2_2") (pintype "passive"))
      (node (ref "C5") (pin "2") (pinfunction "2_2") (pintype "passive"))
      (node (ref "C6") (pin "2") (pinfunction "2_2") (pintype "passive"))
      (node (ref "C7") (pin "2") (pinfunction "2_2") (pintype "passive"))
      (node (ref "C8") (pin "-") (pinfunction "-_-") (pintype "passive"))
      (node (ref "J1") (pin "1") (pinfunction "1_1") (pintype "passive"))
      (node (ref "MS2") (pin "4") (pinfunction "GND_4") (pintype "power_in"))
      (node (ref "Q6") (pin "3") (pinfunction "S_3") (pintype "bidirectional"))
      (node (ref "Q7") (pin "3") (pinfunction "S_3") (pintype "bidirectional"))
      (node (ref "R11") (pin "P$1") (pinfunction "1_P$1") (pintype "passive"))
      (node (ref "R12") (pin "P$1") (pinfunction "1_P$1") (pintype "passive"))
      (node (ref "R13") (pin "P$1") (pinfunction "1_P$1") (pintype "passive"))
      (node (ref "R15") (pin "P$1") (pinfunction "1_P$1") (pintype "passive"))
      (node (ref "R2") (pin "P$1") (pinfunction "1_P$1") (pintype "passive"))
      (node (ref "R5") (pin "P$1") (pinfunction "1_P$1") (pintype "passive"))
      (node (ref "R6") (pin "P$1") (pinfunction "1_P$1") (pintype "passive"))
      (node (ref "R7") (pin "P$1") (pinfunction "1_P$1") (pintype "passive"))
      (node (ref "S1") (pin "P1") (pinfunction "P$1_P1") (pintype "bidirectional"))
      (node (ref "S2") (pin "P1") (pinfunction "P$1_P1") (pintype "bidirectional"))
      (node (ref "U$31") (pin "1") (pinfunction "1_1") (pintype "passive"))
      (node (ref "U$45") (pin "GND") (pinfunction "GND_GND") (pintype "bidirectional"))
      (node (ref "U1") (pin "15") (pinfunction "CLK_INH_15") (pintype "input"))
      (node (ref "U1") (pin "8") (pinfunction "GND_8") (pintype "power_in"))
      (node (ref "U2") (pin "15") (pinfunction "CLK_INH_15") (pintype "input"))
      (node (ref "U2") (pin "8") (pinfunction "GND_8") (pintype "power_in"))
      (node (ref "U3") (pin "15") (pinfunction "CLK_INH_15") (pintype "input"))
      (node (ref "U3") (pin "8") (pinfunction "GND_8") (pintype "power_in"))
      (node (ref "U4") (pin "15") (pinfunction "CLK_INH_15") (pintype "input"))
      (node (ref "U4") (pin "8") (pinfunction "GND_8") (pintype "power_in"))
      (node (ref "U5") (pin "15") (pinfunction "CLK_INH_15") (pintype "input"))
      (node (ref "U5") (pin "8") (pinfunction "GND_8") (pintype "power_in"))
      (node (ref "U6") (pin "15") (pinfunction "CLK_INH_15") (pintype "input"))
      (node (ref "U6") (pin "8") (pinfunction "GND_8") (pintype "power_in"))
      (node (ref "U7") (pin "GND") (pinfunction "GND_GND") (pintype "input"))
    )
    (net (code "43") (name "Net-(Q6-D)") (class "Default")
      (node (ref "Q6") (pin "2") (pinfunction "D_2") (pintype "bidirectional"))
      (node (ref "U$34") (pin "P$1") (pinfunction "1_P$1") (pintype "passive"))
      (node (ref "U$35") (pin "P$1") (pinfunction "1_P$1") (pintype "passive"))
    )
    (net (code "44") (name "Net-(Q7-D)") (class "Default")
      (node (ref "Q7") (pin "2") (pinfunction "D_2") (pintype "bidirectional"))
      (node (ref "U$36") (pin "P$1") (pinfunction "1_P$1") (pintype "passive"))
      (node (ref "U$37") (pin "P$1") (pinfunction "1_P$1") (pintype "passive"))
    )
    (net (code "45") (name "Net-(R2-2)") (class "Default")
      (node (ref "R2") (pin "P$2") (pinfunction "2_P$2") (pintype "passive"))
      (node (ref "U$70") (pin "4") (pinfunction "E_4") (pintype "bidirectional"))
      (node (ref "U1") (pin "3") (pinfunction "E_3") (pintype "tri_state"))
    )
    (net (code "46") (name "Net-(R2-3)") (class "Default")
      (node (ref "R2") (pin "P$3") (pinfunction "3_P$3") (pintype "passive"))
      (node (ref "U$71") (pin "4") (pinfunction "E_4") (pintype "bidirectional"))
      (node (ref "U1") (pin "4") (pinfunction "F_4") (pintype "tri_state"))
    )
    (net (code "47") (name "Net-(R2-4)") (class "Default")
      (node (ref "R2") (pin "P$4") (pinfunction "4_P$4") (pintype "passive"))
      (node (ref "U$69") (pin "4") (pinfunction "E_4") (pintype "bidirectional"))
      (node (ref "U1") (pin "6") (pinfunction "H_6") (pintype "tri_state"))
    )
    (net (code "48") (name "Net-(R2-5)") (class "Default")
      (node (ref "R2") (pin "P$5") (pinfunction "5_P$5") (pintype "passive"))
      (node (ref "U$68") (pin "4") (pinfunction "E_4") (pintype "bidirectional"))
      (node (ref "U1") (pin "5") (pinfunction "G_5") (pintype "tri_state"))
    )
    (net (code "49") (name "Net-(R2-6)") (class "Default")
      (node (ref "R2") (pin "P$6") (pinfunction "6_P$6") (pintype "passive"))
      (node (ref "U$73") (pin "4") (pinfunction "E_4") (pintype "bidirectional"))
      (node (ref "U1") (pin "14") (pinfunction "D_14") (pintype "tri_state"))
    )
    (net (code "50") (name "Net-(R2-7)") (class "Default")
      (node (ref "R2") (pin "P$7") (pinfunction "7_P$7") (pintype "passive"))
      (node (ref "U$72") (pin "4") (pinfunction "E_4") (pintype "bidirectional"))
      (node (ref "U1") (pin "13") (pinfunction "C_13") (pintype "tri_state"))
    )
    (net (code "51") (name "Net-(R2-8)") (class "Default")
      (node (ref "R2") (pin "P$8") (pinfunction "8_P$8") (pintype "passive"))
      (node (ref "U$75") (pin "4") (pinfunction "E_4") (pintype "bidirectional"))
      (node (ref "U1") (pin "12") (pinfunction "B_12") (pintype "tri_state"))
    )
    (net (code "52") (name "Net-(R2-9)") (class "Default")
      (node (ref "R2") (pin "P$9") (pinfunction "9_P$9") (pintype "passive"))
      (node (ref "U$74") (pin "4") (pinfunction "E_4") (pintype "bidirectional"))
      (node (ref "U1") (pin "11") (pinfunction "A_11") (pintype "tri_state"))
    )
    (net (code "53") (name "Net-(R5-2)") (class "Default")
      (node (ref "R5") (pin "P$2") (pinfunction "2_P$2") (pintype "passive"))
      (node (ref "U$82") (pin "4") (pinfunction "E_4") (pintype "bidirectional"))
      (node (ref "U2") (pin "11") (pinfunction "A_11") (pintype "tri_state"))
    )
    (net (code "54") (name "Net-(R5-3)") (class "Default")
      (node (ref "R5") (pin "P$3") (pinfunction "3_P$3") (pintype "passive"))
      (node (ref "U$83") (pin "4") (pinfunction "E_4") (pintype "bidirectional"))
      (node (ref "U2") (pin "12") (pinfunction "B_12") (pintype "tri_state"))
    )
    (net (code "55") (name "Net-(R5-4)") (class "Default")
      (node (ref "R5") (pin "P$4") (pinfunction "4_P$4") (pintype "passive"))
      (node (ref "U$80") (pin "4") (pinfunction "E_4") (pintype "bidirectional"))
      (node (ref "U2") (pin "13") (pinfunction "C_13") (pintype "tri_state"))
    )
    (net (code "56") (name "Net-(R5-5)") (class "Default")
      (node (ref "R5") (pin "P$5") (pinfunction "5_P$5") (pintype "passive"))
      (node (ref "U$81") (pin "4") (pinfunction "E_4") (pintype "bidirectional"))
      (node (ref "U2") (pin "14") (pinfunction "D_14") (pintype "tri_state"))
    )
    (net (code "57") (name "Net-(R5-6)") (class "Default")
      (node (ref "R5") (pin "P$6") (pinfunction "6_P$6") (pintype "passive"))
      (node (ref "U$78") (pin "4") (pinfunction "E_4") (pintype "bidirectional"))
      (node (ref "U2") (pin "3") (pinfunction "E_3") (pintype "tri_state"))
    )
    (net (code "58") (name "Net-(R5-7)") (class "Default")
      (node (ref "R5") (pin "P$7") (pinfunction "7_P$7") (pintype "passive"))
      (node (ref "U$79") (pin "4") (pinfunction "E_4") (pintype "bidirectional"))
      (node (ref "U2") (pin "4") (pinfunction "F_4") (pintype "tri_state"))
    )
    (net (code "59") (name "Net-(R5-8)") (class "Default")
      (node (ref "R5") (pin "P$8") (pinfunction "8_P$8") (pintype "passive"))
      (node (ref "U$76") (pin "4") (pinfunction "E_4") (pintype "bidirectional"))
      (node (ref "U2") (pin "5") (pinfunction "G_5") (pintype "tri_state"))
    )
    (net (code "60") (name "Net-(R5-9)") (class "Default")
      (node (ref "R5") (pin "P$9") (pinfunction "9_P$9") (pintype "passive"))
      (node (ref "U$77") (pin "4") (pinfunction "E_4") (pintype "bidirectional"))
      (node (ref "U2") (pin "6") (pinfunction "H_6") (pintype "tri_state"))
    )
    (net (code "61") (name "Net-(R6-2)") (class "Default")
      (node (ref "R6") (pin "P$2") (pinfunction "2_P$2") (pintype "passive"))
      (node (ref "U$91") (pin "4") (pinfunction "E_4") (pintype "bidirectional"))
      (node (ref "U3") (pin "12") (pinfunction "B_12") (pintype "tri_state"))
    )
    (net (code "62") (name "Net-(R6-3)") (class "Default")
      (node (ref "R6") (pin "P$3") (pinfunction "3_P$3") (pintype "passive"))
      (node (ref "U$90") (pin "4") (pinfunction "E_4") (pintype "bidirectional"))
      (node (ref "U3") (pin "11") (pinfunction "A_11") (pintype "tri_state"))
    )
    (net (code "63") (name "Net-(R6-4)") (class "Default")
      (node (ref "R6") (pin "P$4") (pinfunction "4_P$4") (pintype "passive"))
      (node (ref "U$88") (pin "4") (pinfunction "E_4") (pintype "bidirectional"))
      (node (ref "U3") (pin "13") (pinfunction "C_13") (pintype "tri_state"))
    )
    (net (code "64") (name "Net-(R6-5)") (class "Default")
      (node (ref "R6") (pin "P$5") (pinfunction "5_P$5") (pintype "passive"))
      (node (ref "U$89") (pin "4") (pinfunction "E_4") (pintype "bidirectional"))
      (node (ref "U3") (pin "14") (pinfunction "D_14") (pintype "tri_state"))
    )
    (net (code "65") (name "Net-(R6-6)") (class "Default")
      (node (ref "R6") (pin "P$6") (pinfunction "6_P$6") (pintype "passive"))
      (node (ref "U$86") (pin "4") (pinfunction "E_4") (pintype "bidirectional"))
      (node (ref "U3") (pin "3") (pinfunction "E_3") (pintype "tri_state"))
    )
    (net (code "66") (name "Net-(R6-7)") (class "Default")
      (node (ref "R6") (pin "P$7") (pinfunction "7_P$7") (pintype "passive"))
      (node (ref "U$87") (pin "4") (pinfunction "E_4") (pintype "bidirectional"))
      (node (ref "U3") (pin "4") (pinfunction "F_4") (pintype "tri_state"))
    )
    (net (code "67") (name "Net-(R6-8)") (class "Default")
      (node (ref "R6") (pin "P$8") (pinfunction "8_P$8") (pintype "passive"))
      (node (ref "U$84") (pin "4") (pinfunction "E_4") (pintype "bidirectional"))
      (node (ref "U3") (pin "5") (pinfunction "G_5") (pintype "tri_state"))
    )
    (net (code "68") (name "Net-(R6-9)") (class "Default")
      (node (ref "R6") (pin "P$9") (pinfunction "9_P$9") (pintype "passive"))
      (node (ref "U$85") (pin "4") (pinfunction "E_4") (pintype "bidirectional"))
      (node (ref "U3") (pin "6") (pinfunction "H_6") (pintype "tri_state"))
    )
    (net (code "69") (name "Net-(R7-2)") (class "Default")
      (node (ref "R7") (pin "P$2") (pinfunction "2_P$2") (pintype "passive"))
      (node (ref "U$98") (pin "4") (pinfunction "E_4") (pintype "bidirectional"))
      (node (ref "U4") (pin "11") (pinfunction "A_11") (pintype "tri_state"))
    )
    (net (code "70") (name "Net-(R7-3)") (class "Default")
      (node (ref "R7") (pin "P$3") (pinfunction "3_P$3") (pintype "passive"))
      (node (ref "U$99") (pin "4") (pinfunction "E_4") (pintype "bidirectional"))
      (node (ref "U4") (pin "12") (pinfunction "B_12") (pintype "tri_state"))
    )
    (net (code "71") (name "Net-(R7-4)") (class "Default")
      (node (ref "R7") (pin "P$4") (pinfunction "4_P$4") (pintype "passive"))
      (node (ref "U$96") (pin "4") (pinfunction "E_4") (pintype "bidirectional"))
      (node (ref "U4") (pin "13") (pinfunction "C_13") (pintype "tri_state"))
    )
    (net (code "72") (name "Net-(R7-5)") (class "Default")
      (node (ref "R7") (pin "P$5") (pinfunction "5_P$5") (pintype "passive"))
      (node (ref "U$97") (pin "4") (pinfunction "E_4") (pintype "bidirectional"))
      (node (ref "U4") (pin "14") (pinfunction "D_14") (pintype "tri_state"))
    )
    (net (code "73") (name "Net-(R7-6)") (class "Default")
      (node (ref "R7") (pin "P$6") (pinfunction "6_P$6") (pintype "passive"))
      (node (ref "U$94") (pin "4") (pinfunction "E_4") (pintype "bidirectional"))
      (node (ref "U4") (pin "3") (pinfunction "E_3") (pintype "tri_state"))
    )
    (net (code "74") (name "Net-(R7-7)") (class "Default")
      (node (ref "R7") (pin "P$7") (pinfunction "7_P$7") (pintype "passive"))
      (node (ref "U$95") (pin "4") (pinfunction "E_4") (pintype "bidirectional"))
      (node (ref "U4") (pin "4") (pinfunction "F_4") (pintype "tri_state"))
    )
    (net (code "75") (name "Net-(R7-8)") (class "Default")
      (node (ref "R7") (pin "P$8") (pinfunction "8_P$8") (pintype "passive"))
      (node (ref "U$92") (pin "4") (pinfunction "E_4") (pintype "bidirectional"))
      (node (ref "U4") (pin "5") (pinfunction "G_5") (pintype "tri_state"))
    )
    (net (code "76") (name "Net-(R7-9)") (class "Default")
      (node (ref "R7") (pin "P$9") (pinfunction "9_P$9") (pintype "passive"))
      (node (ref "U$93") (pin "4") (pinfunction "E_4") (pintype "bidirectional"))
      (node (ref "U4") (pin "6") (pinfunction "H_6") (pintype "tri_state"))
    )
    (net (code "77") (name "Net-(R11-2)") (class "Default")
      (node (ref "R11") (pin "P$2") (pinfunction "2_P$2") (pintype "passive"))
      (node (ref "U$106") (pin "4") (pinfunction "E_4") (pintype "bidirectional"))
      (node (ref "U5") (pin "11") (pinfunction "A_11") (pintype "tri_state"))
    )
    (net (code "78") (name "Net-(R11-3)") (class "Default")
      (node (ref "R11") (pin "P$3") (pinfunction "3_P$3") (pintype "passive"))
      (node (ref "U$107") (pin "4") (pinfunction "E_4") (pintype "bidirectional"))
      (node (ref "U5") (pin "12") (pinfunction "B_12") (pintype "tri_state"))
    )
    (net (code "79") (name "Net-(R11-4)") (class "Default")
      (node (ref "R11") (pin "P$4") (pinfunction "4_P$4") (pintype "passive"))
      (node (ref "U$104") (pin "4") (pinfunction "E_4") (pintype "bidirectional"))
      (node (ref "U5") (pin "13") (pinfunction "C_13") (pintype "tri_state"))
    )
    (net (code "80") (name "Net-(R11-5)") (class "Default")
      (node (ref "R11") (pin "P$5") (pinfunction "5_P$5") (pintype "passive"))
      (node (ref "U$105") (pin "4") (pinfunction "E_4") (pintype "bidirectional"))
      (node (ref "U5") (pin "14") (pinfunction "D_14") (pintype "tri_state"))
    )
    (net (code "81") (name "Net-(R11-6)") (class "Default")
      (node (ref "R11") (pin "P$6") (pinfunction "6_P$6") (pintype "passive"))
      (node (ref "U$102") (pin "4") (pinfunction "E_4") (pintype "bidirectional"))
      (node (ref "U5") (pin "3") (pinfunction "E_3") (pintype "tri_state"))
    )
    (net (code "82") (name "Net-(R11-7)") (class "Default")
      (node (ref "R11") (pin "P$7") (pinfunction "7_P$7") (pintype "passive"))
      (node (ref "U$103") (pin "4") (pinfunction "E_4") (pintype "bidirectional"))
      (node (ref "U5") (pin "4") (pinfunction "F_4") (pintype "tri_state"))
    )
    (net (code "83") (name "Net-(R11-8)") (class "Default")
      (node (ref "R11") (pin "P$8") (pinfunction "8_P$8") (pintype "passive"))
      (node (ref "U$100") (pin "4") (pinfunction "E_4") (pintype "bidirectional"))
      (node (ref "U5") (pin "5") (pinfunction "G_5") (pintype "tri_state"))
    )
    (net (code "84") (name "Net-(R11-9)") (class "Default")
      (node (ref "R11") (pin "P$9") (pinfunction "9_P$9") (pintype "passive"))
      (node (ref "U$101") (pin "4") (pinfunction "E_4") (pintype "bidirectional"))
      (node (ref "U5") (pin "6") (pinfunction "H_6") (pintype "tri_state"))
    )
    (net (code "85") (name "Net-(R12-2)") (class "Default")
      (node (ref "R12") (pin "P$2") (pinfunction "2_P$2") (pintype "passive"))
      (node (ref "U$115") (pin "4") (pinfunction "E_4") (pintype "bidirectional"))
      (node (ref "U6") (pin "12") (pinfunction "B_12") (pintype "tri_state"))
    )
    (net (code "86") (name "Net-(R12-3)") (class "Default")
      (node (ref "R12") (pin "P$3") (pinfunction "3_P$3") (pintype "passive"))
      (node (ref "U$114") (pin "4") (pinfunction "E_4") (pintype "bidirectional"))
      (node (ref "U6") (pin "11") (pinfunction "A_11") (pintype "tri_state"))
    )
    (net (code "87") (name "Net-(R12-4)") (class "Default")
      (node (ref "R12") (pin "P$4") (pinfunction "4_P$4") (pintype "passive"))
      (node (ref "U$112") (pin "4") (pinfunction "E_4") (pintype "bidirectional"))
      (node (ref "U6") (pin "13") (pinfunction "C_13") (pintype "tri_state"))
    )
    (net (code "88") (name "Net-(R12-5)") (class "Default")
      (node (ref "R12") (pin "P$5") (pinfunction "5_P$5") (pintype "passive"))
      (node (ref "U$113") (pin "4") (pinfunction "E_4") (pintype "bidirectional"))
      (node (ref "U6") (pin "14") (pinfunction "D_14") (pintype "tri_state"))
    )
    (net (code "89") (name "Net-(R12-6)") (class "Default")
      (node (ref "R12") (pin "P$6") (pinfunction "6_P$6") (pintype "passive"))
      (node (ref "U$110") (pin "4") (pinfunction "E_4") (pintype "bidirectional"))
      (node (ref "U6") (pin "3") (pinfunction "E_3") (pintype "tri_state"))
    )
    (net (code "90") (name "Net-(R12-7)") (class "Default")
      (node (ref "R12") (pin "P$7") (pinfunction "7_P$7") (pintype "passive"))
      (node (ref "U$111") (pin "4") (pinfunction "E_4") (pintype "bidirectional"))
      (node (ref "U6") (pin "4") (pinfunction "F_4") (pintype "tri_state"))
    )
    (net (code "91") (name "Net-(R12-8)") (class "Default")
      (node (ref "R12") (pin "P$8") (pinfunction "8_P$8") (pintype "passive"))
      (node (ref "U$108") (pin "4") (pinfunction "E_4") (pintype "bidirectional"))
      (node (ref "U6") (pin "5") (pinfunction "G_5") (pintype "tri_state"))
    )
    (net (code "92") (name "Net-(R12-9)") (class "Default")
      (node (ref "R12") (pin "P$9") (pinfunction "9_P$9") (pintype "passive"))
      (node (ref "U$109") (pin "4") (pinfunction "E_4") (pintype "bidirectional"))
      (node (ref "U6") (pin "6") (pinfunction "H_6") (pintype "tri_state"))
    )
    (net (code "93") (name "Net-(U$68-K)") (class "Default")
      (node (ref "U$68") (pin "2") (pinfunction "K_2") (pintype "bidirectional"))
      (node (ref "U$69") (pin "1") (pinfunction "A_1") (pintype "bidirectional"))
    )
    (net (code "94") (name "Net-(U$70-K)") (class "Default")
      (node (ref "U$70") (pin "2") (pinfunction "K_2") (pintype "bidirectional"))
      (node (ref "U$71") (pin "1") (pinfunction "A_1") (pintype "bidirectional"))
    )
    (net (code "95") (name "Net-(U$72-K)") (class "Default")
      (node (ref "U$72") (pin "2") (pinfunction "K_2") (pintype "bidirectional"))
      (node (ref "U$73") (pin "1") (pinfunction "A_1") (pintype "bidirectional"))
    )
    (net (code "96") (name "Net-(U$74-K)") (class "Default")
      (node (ref "U$74") (pin "2") (pinfunction "K_2") (pintype "bidirectional"))
      (node (ref "U$75") (pin "1") (pinfunction "A_1") (pintype "bidirectional"))
    )
    (net (code "97") (name "Net-(U$76-K)") (class "Default")
      (node (ref "U$76") (pin "2") (pinfunction "K_2") (pintype "bidirectional"))
      (node (ref "U$77") (pin "1") (pinfunction "A_1") (pintype "bidirectional"))
    )
    (net (code "98") (name "Net-(U$78-K)") (class "Default")
      (node (ref "U$78") (pin "2") (pinfunction "K_2") (pintype "bidirectional"))
      (node (ref "U$79") (pin "1") (pinfunction "A_1") (pintype "bidirectional"))
    )
    (net (code "99") (name "Net-(U$80-K)") (class "Default")
      (node (ref "U$80") (pin "2") (pinfunction "K_2") (pintype "bidirectional"))
      (node (ref "U$81") (pin "1") (pinfunction "A_1") (pintype "bidirectional"))
    )
    (net (code "100") (name "Net-(U$82-K)") (class "Default")
      (node (ref "U$82") (pin "2") (pinfunction "K_2") (pintype "bidirectional"))
      (node (ref "U$83") (pin "1") (pinfunction "A_1") (pintype "bidirectional"))
    )
    (net (code "101") (name "Net-(U$84-K)") (class "Default")
      (node (ref "U$84") (pin "2") (pinfunction "K_2") (pintype "bidirectional"))
      (node (ref "U$85") (pin "1") (pinfunction "A_1") (pintype "bidirectional"))
    )
    (net (code "102") (name "Net-(U$86-K)") (class "Default")
      (node (ref "U$86") (pin "2") (pinfunction "K_2") (pintype "bidirectional"))
      (node (ref "U$87") (pin "1") (pinfunction "A_1") (pintype "bidirectional"))
    )
    (net (code "103") (name "Net-(U$88-K)") (class "Default")
      (node (ref "U$88") (pin "2") (pinfunction "K_2") (pintype "bidirectional"))
      (node (ref "U$89") (pin "1") (pinfunction "A_1") (pintype "bidirectional"))
    )
    (net (code "104") (name "Net-(U$90-K)") (class "Default")
      (node (ref "U$90") (pin "2") (pinfunction "K_2") (pintype "bidirectional"))
      (node (ref "U$91") (pin "1") (pinfunction "A_1") (pintype "bidirectional"))
    )
    (net (code "105") (name "Net-(U$92-K)") (class "Default")
      (node (ref "U$92") (pin "2") (pinfunction "K_2") (pintype "bidirectional"))
      (node (ref "U$93") (pin "1") (pinfunction "A_1") (pintype "bidirectional"))
    )
    (net (code "106") (name "Net-(U$94-K)") (class "Default")
      (node (ref "U$94") (pin "2") (pinfunction "K_2") (pintype "bidirectional"))
      (node (ref "U$95") (pin "1") (pinfunction "A_1") (pintype "bidirectional"))
    )
    (net (code "107") (name "Net-(U$96-K)") (class "Default")
      (node (ref "U$96") (pin "2") (pinfunction "K_2") (pintype "bidirectional"))
      (node (ref "U$97") (pin "1") (pinfunction "A_1") (pintype "bidirectional"))
    )
    (net (code "108") (name "Net-(U$98-K)") (class "Default")
      (node (ref "U$98") (pin "2") (pinfunction "K_2") (pintype "bidirectional"))
      (node (ref "U$99") (pin "1") (pinfunction "A_1") (pintype "bidirectional"))
    )
    (net (code "109") (name "Net-(U$100-K)") (class "Default")
      (node (ref "U$100") (pin "2") (pinfunction "K_2") (pintype "bidirectional"))
      (node (ref "U$101") (pin "1") (pinfunction "A_1") (pintype "bidirectional"))
    )
    (net (code "110") (name "Net-(U$102-K)") (class "Default")
      (node (ref "U$102") (pin "2") (pinfunction "K_2") (pintype "bidirectional"))
      (node (ref "U$103") (pin "1") (pinfunction "A_1") (pintype "bidirectional"))
    )
    (net (code "111") (name "Net-(U$104-K)") (class "Default")
      (node (ref "U$104") (pin "2") (pinfunction "K_2") (pintype "bidirectional"))
      (node (ref "U$105") (pin "1") (pinfunction "A_1") (pintype "bidirectional"))
    )
    (net (code "112") (name "Net-(U$106-K)") (class "Default")
      (node (ref "U$106") (pin "2") (pinfunction "K_2") (pintype "bidirectional"))
      (node (ref "U$107") (pin "1") (pinfunction "A_1") (pintype "bidirectional"))
    )
    (net (code "113") (name "Net-(U$108-K)") (class "Default")
      (node (ref "U$108") (pin "2") (pinfunction "K_2") (pintype "bidirectional"))
      (node (ref "U$109") (pin "1") (pinfunction "A_1") (pintype "bidirectional"))
    )
    (net (code "114") (name "Net-(U$110-K)") (class "Default")
      (node (ref "U$110") (pin "2") (pinfunction "K_2") (pintype "bidirectional"))
      (node (ref "U$111") (pin "1") (pinfunction "A_1") (pintype "bidirectional"))
    )
    (net (code "115") (name "Net-(U$112-K)") (class "Default")
      (node (ref "U$112") (pin "2") (pinfunction "K_2") (pintype "bidirectional"))
      (node (ref "U$113") (pin "1") (pinfunction "A_1") (pintype "bidirectional"))
    )
    (net (code "116") (name "Net-(U$114-K)") (class "Default")
      (node (ref "U$114") (pin "2") (pinfunction "K_2") (pintype "bidirectional"))
      (node (ref "U$115") (pin "1") (pinfunction "A_1") (pintype "bidirectional"))
    )
    (net (code "117") (name "Net-(U3-QH)") (class "Default")
      (node (ref "U3") (pin "9") (pinfunction "QH_9") (pintype "tri_state"))
      (node (ref "U4") (pin "10") (pinfunction "SER_10") (pintype "input"))
    )
    (net (code "118") (name "unconnected-(MS2-AREF-Pad3)") (class "Default")
      (node (ref "MS2") (pin "3") (pinfunction "AREF_3") (pintype "passive"))
    )
    (net (code "119") (name "unconnected-(MS2-EN-Pad27)") (class "Default")
      (node (ref "MS2") (pin "27") (pinfunction "EN_27") (pintype "passive"))
    )
    (net (code "120") (name "unconnected-(MS2-GPIO5-Pad19)") (class "Default")
      (node (ref "MS2") (pin "19") (pinfunction "GPIO5_19") (pintype "bidirectional"))
    )
    (net (code "121") (name "unconnected-(MS2-GPIO6-Pad20)") (class "Default")
      (node (ref "MS2") (pin "20") (pinfunction "GPIO6_20") (pintype "bidirectional"))
    )
    (net (code "122") (name "unconnected-(MS2-GPIO11-Pad23)") (class "Default")
      (node (ref "MS2") (pin "23") (pinfunction "GPIO11_23") (pintype "bidirectional"))
    )
    (net (code "123") (name "unconnected-(MS2-GPIO12-Pad24)") (class "Default")
      (node (ref "MS2") (pin "24") (pinfunction "GPIO12_24") (pintype "bidirectional"))
    )
    (net (code "124") (name "unconnected-(MS2-GPIO13-Pad25)") (class "Default")
      (node (ref "MS2") (pin "25") (pinfunction "GPIO13_25") (pintype "bidirectional"))
    )
    (net (code "125") (name "unconnected-(MS2-GPIOA0-Pad5)") (class "Default")
      (node (ref "MS2") (pin "5") (pinfunction "GPIOA0_5") (pintype "bidirectional"))
    )
    (net (code "126") (name "unconnected-(MS2-GPIOA1-Pad6)") (class "Default")
      (node (ref "MS2") (pin "6") (pinfunction "GPIOA1_6") (pintype "bidirectional"))
    )
    (net (code "127") (name "unconnected-(MS2-GPIOA2-Pad7)") (class "Default")
      (node (ref "MS2") (pin "7") (pinfunction "GPIOA2_7") (pintype "bidirectional"))
    )
    (net (code "128") (name "unconnected-(MS2-GPIOA3-Pad8)") (class "Default")
      (node (ref "MS2") (pin "8") (pinfunction "GPIOA3_8") (pintype "bidirectional"))
    )
    (net (code "129") (name "unconnected-(MS2-GPIOMOSI-Pad12)") (class "Default")
      (node (ref "MS2") (pin "12") (pinfunction "GPIOMOSI_12") (pintype "bidirectional"))
    )
    (net (code "130") (name "unconnected-(MS2-GPIORX-Pad14)") (class "Default")
      (node (ref "MS2") (pin "14") (pinfunction "GPIORX_14") (pintype "bidirectional"))
    )
    (net (code "131") (name "unconnected-(MS2-GPIOTX-Pad15)") (class "Default")
      (node (ref "MS2") (pin "15") (pinfunction "GPIOTX_15") (pintype "bidirectional"))
    )
    (net (code "132") (name "unconnected-(MS2-NC-Pad16)") (class "Default")
      (node (ref "MS2") (pin "16") (pinfunction "NC_16") (pintype "passive"))
    )
    (net (code "133") (name "unconnected-(MS2-~{RESET}-Pad1)") (class "Default")
      (node (ref "MS2") (pin "1") (pinfunction "~{RESET}_1") (pintype "input"))
    )
    (net (code "134") (name "unconnected-(U$1-4-Pad1)") (class "Default")
      (node (ref "U$1") (pin "1") (pinfunction "4_1") (pintype "passive"))
    )
    (net (code "135") (name "unconnected-(U$1-Pad6)") (class "Default")
      (node (ref "U$1") (pin "6") (pinfunction "6_6") (pintype "passive"))
    )
    (net (code "136") (name "unconnected-(U$2-4-Pad1)") (class "Default")
      (node (ref "U$2") (pin "1") (pinfunction "4_1") (pintype "passive"))
    )
    (net (code "137") (name "unconnected-(U$2-Pad6)") (class "Default")
      (node (ref "U$2") (pin "6") (pinfunction "6_6") (pintype "passive"))
    )
    (net (code "138") (name "unconnected-(U$3-4-Pad1)") (class "Default")
      (node (ref "U$3") (pin "1") (pinfunction "4_1") (pintype "passive"))
    )
    (net (code "139") (name "unconnected-(U$3-Pad6)") (class "Default")
      (node (ref "U$3") (pin "6") (pinfunction "6_6") (pintype "passive"))
    )
    (net (code "140") (name "unconnected-(U$4-4-Pad1)") (class "Default")
      (node (ref "U$4") (pin "1") (pinfunction "4_1") (pintype "passive"))
    )
    (net (code "141") (name "unconnected-(U$4-Pad6)") (class "Default")
      (node (ref "U$4") (pin "6") (pinfunction "6_6") (pintype "passive"))
    )
    (net (code "142") (name "unconnected-(U$5-4-Pad1)") (class "Default")
      (node (ref "U$5") (pin "1") (pinfunction "4_1") (pintype "passive"))
    )
    (net (code "143") (name "unconnected-(U$5-Pad6)") (class "Default")
      (node (ref "U$5") (pin "6") (pinfunction "6_6") (pintype "passive"))
    )
    (net (code "144") (name "unconnected-(U$6-4-Pad1)") (class "Default")
      (node (ref "U$6") (pin "1") (pinfunction "4_1") (pintype "passive"))
    )
    (net (code "145") (name "unconnected-(U$6-Pad6)") (class "Default")
      (node (ref "U$6") (pin "6") (pinfunction "6_6") (pintype "passive"))
    )
    (net (code "146") (name "unconnected-(U$7-4-Pad1)") (class "Default")
      (node (ref "U$7") (pin "1") (pinfunction "4_1") (pintype "passive"))
    )
    (net (code "147") (name "unconnected-(U$7-Pad6)") (class "Default")
      (node (ref "U$7") (pin "6") (pinfunction "6_6") (pintype "passive"))
    )
    (net (code "148") (name "unconnected-(U$8-4-Pad1)") (class "Default")
      (node (ref "U$8") (pin "1") (pinfunction "4_1") (pintype "passive"))
    )
    (net (code "149") (name "unconnected-(U$8-Pad6)") (class "Default")
      (node (ref "U$8") (pin "6") (pinfunction "6_6") (pintype "passive"))
    )
    (net (code "150") (name "unconnected-(U$9-4-Pad1)") (class "Default")
      (node (ref "U$9") (pin "1") (pinfunction "4_1") (pintype "passive"))
    )
    (net (code "151") (name "unconnected-(U$9-Pad6)") (class "Default")
      (node (ref "U$9") (pin "6") (pinfunction "6_6") (pintype "passive"))
    )
    (net (code "152") (name "unconnected-(U$10-4-Pad1)") (class "Default")
      (node (ref "U$10") (pin "1") (pinfunction "4_1") (pintype "passive"))
    )
    (net (code "153") (name "unconnected-(U$10-Pad6)") (class "Default")
      (node (ref "U$10") (pin "6") (pinfunction "6_6") (pintype "passive"))
    )
    (net (code "154") (name "unconnected-(U$11-4-Pad1)") (class "Default")
      (node (ref "U$11") (pin "1") (pinfunction "4_1") (pintype "passive"))
    )
    (net (code "155") (name "unconnected-(U$11-Pad6)") (class "Default")
      (node (ref "U$11") (pin "6") (pinfunction "6_6") (pintype "passive"))
    )
    (net (code "156") (name "unconnected-(U$12-4-Pad1)") (class "Default")
      (node (ref "U$12") (pin "1") (pinfunction "4_1") (pintype "passive"))
    )
    (net (code "157") (name "unconnected-(U$12-Pad6)") (class "Default")
      (node (ref "U$12") (pin "6") (pinfunction "6_6") (pintype "passive"))
    )
    (net (code "158") (name "unconnected-(U$13-4-Pad1)") (class "Default")
      (node (ref "U$13") (pin "1") (pinfunction "4_1") (pintype "passive"))
    )
    (net (code "159") (name "unconnected-(U$13-Pad6)") (class "Default")
      (node (ref "U$13") (pin "6") (pinfunction "6_6") (pintype "passive"))
    )
    (net (code "160") (name "unconnected-(U$14-4-Pad1)") (class "Default")
      (node (ref "U$14") (pin "1") (pinfunction "4_1") (pintype "passive"))
    )
    (net (code "161") (name "unconnected-(U$14-Pad6)") (class "Default")
      (node (ref "U$14") (pin "6") (pinfunction "6_6") (pintype "passive"))
    )
    (net (code "162") (name "unconnected-(U$15-4-Pad1)") (class "Default")
      (node (ref "U$15") (pin "1") (pinfunction "4_1") (pintype "passive"))
    )
    (net (code "163") (name "unconnected-(U$15-Pad6)") (class "Default")
      (node (ref "U$15") (pin "6") (pinfunction "6_6") (pintype "passive"))
    )
    (net (code "164") (name "unconnected-(U$16-4-Pad1)") (class "Default")
      (node (ref "U$16") (pin "1") (pinfunction "4_1") (pintype "passive"))
    )
    (net (code "165") (name "unconnected-(U$16-Pad6)") (class "Default")
      (node (ref "U$16") (pin "6") (pinfunction "6_6") (pintype "passive"))
    )
    (net (code "166") (name "unconnected-(U$17-4-Pad1)") (class "Default")
      (node (ref "U$17") (pin "1") (pinfunction "4_1") (pintype "passive"))
    )
    (net (code "167") (name "unconnected-(U$17-Pad6)") (class "Default")
      (node (ref "U$17") (pin "6") (pinfunction "6_6") (pintype "passive"))
    )
    (net (code "168") (name "unconnected-(U$18-4-Pad1)") (class "Default")
      (node (ref "U$18") (pin "1") (pinfunction "4_1") (pintype "passive"))
    )
    (net (code "169") (name "unconnected-(U$18-Pad6)") (class "Default")
      (node (ref "U$18") (pin "6") (pinfunction "6_6") (pintype "passive"))
    )
    (net (code "170") (name "unconnected-(U$19-4-Pad1)") (class "Default")
      (node (ref "U$19") (pin "1") (pinfunction "4_1") (pintype "passive"))
    )
    (net (code "171") (name "unconnected-(U$19-Pad6)") (class "Default")
      (node (ref "U$19") (pin "6") (pinfunction "6_6") (pintype "passive"))
    )
    (net (code "172") (name "unconnected-(U$20-4-Pad1)") (class "Default")
      (node (ref "U$20") (pin "1") (pinfunction "4_1") (pintype "passive"))
    )
    (net (code "173") (name "unconnected-(U$20-Pad6)") (class "Default")
      (node (ref "U$20") (pin "6") (pinfunction "6_6") (pintype "passive"))
    )
    (net (code "174") (name "unconnected-(U$21-4-Pad1)") (class "Default")
      (node (ref "U$21") (pin "1") (pinfunction "4_1") (pintype "passive"))
    )
    (net (code "175") (name "unconnected-(U$21-Pad6)") (class "Default")
      (node (ref "U$21") (pin "6") (pinfunction "6_6") (pintype "passive"))
    )
    (net (code "176") (name "unconnected-(U$22-4-Pad1)") (class "Default")
      (node (ref "U$22") (pin "1") (pinfunction "4_1") (pintype "passive"))
    )
    (net (code "177") (name "unconnected-(U$22-Pad6)") (class "Default")
      (node (ref "U$22") (pin "6") (pinfunction "6_6") (pintype "passive"))
    )
    (net (code "178") (name "unconnected-(U$23-4-Pad1)") (class "Default")
      (node (ref "U$23") (pin "1") (pinfunction "4_1") (pintype "passive"))
    )
    (net (code "179") (name "unconnected-(U$23-Pad6)") (class "Default")
      (node (ref "U$23") (pin "6") (pinfunction "6_6") (pintype "passive"))
    )
    (net (code "180") (name "unconnected-(U$24-4-Pad1)") (class "Default")
      (node (ref "U$24") (pin "1") (pinfunction "4_1") (pintype "passive"))
    )
    (net (code "181") (name "unconnected-(U$24-Pad6)") (class "Default")
      (node (ref "U$24") (pin "6") (pinfunction "6_6") (pintype "passive"))
    )
    (net (code "182") (name "unconnected-(U$25-4-Pad1)") (class "Default")
      (node (ref "U$25") (pin "1") (pinfunction "4_1") (pintype "passive"))
    )
    (net (code "183") (name "unconnected-(U$25-Pad6)") (class "Default")
      (node (ref "U$25") (pin "6") (pinfunction "6_6") (pintype "passive"))
    )
    (net (code "184") (name "unconnected-(U$26-4-Pad1)") (class "Default")
      (node (ref "U$26") (pin "1") (pinfunction "4_1") (pintype "passive"))
    )
    (net (code "185") (name "unconnected-(U$26-Pad6)") (class "Default")
      (node (ref "U$26") (pin "6") (pinfunction "6_6") (pintype "passive"))
    )
    (net (code "186") (name "unconnected-(U$27-4-Pad1)") (class "Default")
      (node (ref "U$27") (pin "1") (pinfunction "4_1") (pintype "passive"))
    )
    (net (code "187") (name "unconnected-(U$27-Pad6)") (class "Default")
      (node (ref "U$27") (pin "6") (pinfunction "6_6") (pintype "passive"))
    )
    (net (code "188") (name "unconnected-(U$28-4-Pad1)") (class "Default")
      (node (ref "U$28") (pin "1") (pinfunction "4_1") (pintype "passive"))
    )
    (net (code "189") (name "unconnected-(U$28-Pad6)") (class "Default")
      (node (ref "U$28") (pin "6") (pinfunction "6_6") (pintype "passive"))
    )
    (net (code "190") (name "unconnected-(U$29-4-Pad1)") (class "Default")
      (node (ref "U$29") (pin "1") (pinfunction "4_1") (pintype "passive"))
    )
    (net (code "191") (name "unconnected-(U$29-Pad6)") (class "Default")
      (node (ref "U$29") (pin "6") (pinfunction "6_6") (pintype "passive"))
    )
    (net (code "192") (name "unconnected-(U$30-4-Pad1)") (class "Default")
      (node (ref "U$30") (pin "1") (pinfunction "4_1") (pintype "passive"))
    )
    (net (code "193") (name "unconnected-(U$30-Pad6)") (class "Default")
      (node (ref "U$30") (pin "6") (pinfunction "6_6") (pintype "passive"))
    )
    (net (code "194") (name "unconnected-(U$34-10-PadP$10)") (class "Default")
      (node (ref "U$34") (pin "P$10") (pinfunction "10_P$10") (pintype "passive"))
    )
    (net (code "195") (name "unconnected-(U$35-6-PadP$6)") (class "Default")
      (node (ref "U$35") (pin "P$6") (pinfunction "6_P$6") (pintype "passive"))
    )
    (net (code "196") (name "unconnected-(U$35-7-PadP$7)") (class "Default")
      (node (ref "U$35") (pin "P$7") (pinfunction "7_P$7") (pintype "passive"))
    )
    (net (code "197") (name "unconnected-(U$35-8-PadP$8)") (class "Default")
      (node (ref "U$35") (pin "P$8") (pinfunction "8_P$8") (pintype "passive"))
    )
    (net (code "198") (name "unconnected-(U$35-9-PadP$9)") (class "Default")
      (node (ref "U$35") (pin "P$9") (pinfunction "9_P$9") (pintype "passive"))
    )
    (net (code "199") (name "unconnected-(U$35-10-PadP$10)") (class "Default")
      (node (ref "U$35") (pin "P$10") (pinfunction "10_P$10") (pintype "passive"))
    )
    (net (code "200") (name "unconnected-(U$36-10-PadP$10)") (class "Default")
      (node (ref "U$36") (pin "P$10") (pinfunction "10_P$10") (pintype "passive"))
    )
    (net (code "201") (name "unconnected-(U$37-2-PadP$2)") (class "Default")
      (node (ref "U$37") (pin "P$2") (pinfunction "2_P$2") (pintype "passive"))
    )
    (net (code "202") (name "unconnected-(U$37-3-PadP$3)") (class "Default")
      (node (ref "U$37") (pin "P$3") (pinfunction "3_P$3") (pintype "passive"))
    )
    (net (code "203") (name "unconnected-(U$37-4-PadP$4)") (class "Default")
      (node (ref "U$37") (pin "P$4") (pinfunction "4_P$4") (pintype "passive"))
    )
    (net (code "204") (name "unconnected-(U$37-5-PadP$5)") (class "Default")
      (node (ref "U$37") (pin "P$5") (pinfunction "5_P$5") (pintype "passive"))
    )
    (net (code "205") (name "unconnected-(U$37-10-PadP$10)") (class "Default")
      (node (ref "U$37") (pin "P$10") (pinfunction "10_P$10") (pintype "passive"))
    )
    (net (code "206") (name "unconnected-(U$45-A(0)-PadA0)") (class "Default")
      (node (ref "U$45") (pin "A0") (pinfunction "A(0)_A0") (pintype "bidirectional"))
    )
    (net (code "207") (name "unconnected-(U$45-Pad2)") (class "Default")
      (node (ref "U$45") (pin "2") (pinfunction "2_2") (pintype "bidirectional"))
    )
    (net (code "208") (name "unconnected-(U$45-Pad3V)") (class "Default")
      (node (ref "U$45") (pin "3V") (pinfunction "3V_3V") (pintype "bidirectional"))
    )
    (net (code "209") (name "unconnected-(U$45-PadA1)") (class "Default")
      (node (ref "U$45") (pin "A1") (pinfunction "A1_A1") (pintype "bidirectional"))
    )
    (net (code "210") (name "unconnected-(U$45-PadA2)") (class "Default")
      (node (ref "U$45") (pin "A2") (pinfunction "A2_A2") (pintype "bidirectional"))
    )
    (net (code "211") (name "unconnected-(U$45-PadA3)") (class "Default")
      (node (ref "U$45") (pin "A3") (pinfunction "A3_A3") (pintype "bidirectional"))
    )
    (net (code "212") (name "unconnected-(U$45-PadAREF)") (class "Default")
      (node (ref "U$45") (pin "AREF") (pinfunction "AREF_AREF") (pintype "bidirectional"))
    )
    (net (code "213") (name "unconnected-(U$45-PadD5)") (class "Default")
      (node (ref "U$45") (pin "D5") (pinfunction "D5_D5") (pintype "bidirectional"))
    )
    (net (code "214") (name "unconnected-(U$45-PadD7)") (class "Default")
      (node (ref "U$45") (pin "D7") (pinfunction "D7_D7") (pintype "bidirectional"))
    )
    (net (code "215") (name "unconnected-(U$45-PadD9)") (class "Default")
      (node (ref "U$45") (pin "D9") (pinfunction "D9_D9") (pintype "bidirectional"))
    )
    (net (code "216") (name "unconnected-(U$45-PadD12)") (class "Default")
      (node (ref "U$45") (pin "D12") (pinfunction "D12_D12") (pintype "bidirectional"))
    )
    (net (code "217") (name "unconnected-(U$45-PadD13)") (class "Default")
      (node (ref "U$45") (pin "D13") (pinfunction "D13_D13") (pintype "bidirectional"))
    )
    (net (code "218") (name "unconnected-(U$45-PadMOSI)") (class "Default")
      (node (ref "U$45") (pin "MOSI") (pinfunction "MOSI_MOSI") (pintype "bidirectional"))
    )
    (net (code "219") (name "unconnected-(U$45-PadRES)") (class "Default")
      (node (ref "U$45") (pin "RES") (pinfunction "RES_RES") (pintype "bidirectional"))
    )
    (net (code "220") (name "unconnected-(U$45-PadRX)") (class "Default")
      (node (ref "U$45") (pin "RX") (pinfunction "RX_RX") (pintype "bidirectional"))
    )
    (net (code "221") (name "unconnected-(U$45-PadTX)") (class "Default")
      (node (ref "U$45") (pin "TX") (pinfunction "TX_TX") (pintype "bidirectional"))
    )
    (net (code "222") (name "unconnected-(U$45-PadVHI)") (class "Default")
      (node (ref "U$45") (pin "VHI") (pinfunction "VHI_VHI") (pintype "bidirectional"))
    )
    (net (code "223") (name "unconnected-(U$45-PadVIN)") (class "Default")
      (node (ref "U$45") (pin "VIN") (pinfunction "VIN_VIN") (pintype "bidirectional"))
    )
    (net (code "224") (name "unconnected-(U$59-4-Pad1)") (class "Default")
      (node (ref "U$59") (pin "1") (pinfunction "4_1") (pintype "passive"))
    )
    (net (code "225") (name "unconnected-(U$59-Pad6)") (class "Default")
      (node (ref "U$59") (pin "6") (pinfunction "6_6") (pintype "passive"))
    )
    (net (code "226") (name "unconnected-(U$60-Pad1)") (class "Default")
      (node (ref "U$60") (pin "1") (pinfunction "1_1") (pintype "passive"))
    )
    (net (code "227") (name "unconnected-(U$61-Pad1)") (class "Default")
      (node (ref "U$61") (pin "1") (pinfunction "1_1") (pintype "passive"))
    )
    (net (code "228") (name "unconnected-(U1-SER-Pad10)") (class "Default")
      (node (ref "U1") (pin "10") (pinfunction "SER_10") (pintype "input"))
    )
    (net (code "229") (name "unconnected-(U1-~{QH}-Pad7)") (class "Default")
      (node (ref "U1") (pin "7") (pinfunction "~{QH}_7") (pintype "input"))
    )
    (net (code "230") (name "unconnected-(U2-~{QH}-Pad7)") (class "Default")
      (node (ref "U2") (pin "7") (pinfunction "~{QH}_7") (pintype "input"))
    )
    (net (code "231") (name "unconnected-(U3-~{QH}-Pad7)") (class "Default")
      (node (ref "U3") (pin "7") (pinfunction "~{QH}_7") (pintype "input"))
    )
    (net (code "232") (name "unconnected-(U4-~{QH}-Pad7)") (class "Default")
      (node (ref "U4") (pin "7") (pinfunction "~{QH}_7") (pintype "input"))
    )
    (net (code "233") (name "unconnected-(U5-~{QH}-Pad7)") (class "Default")
      (node (ref "U5") (pin "7") (pinfunction "~{QH}_7") (pintype "input"))
    )
    (net (code "234") (name "unconnected-(U6-~{QH}-Pad7)") (class "Default")
      (node (ref "U6") (pin "7") (pinfunction "~{QH}_7") (pintype "input"))
    )
  )
)
